# TK90X.net
KiCad netlist of a schematic drawn in EAGLE
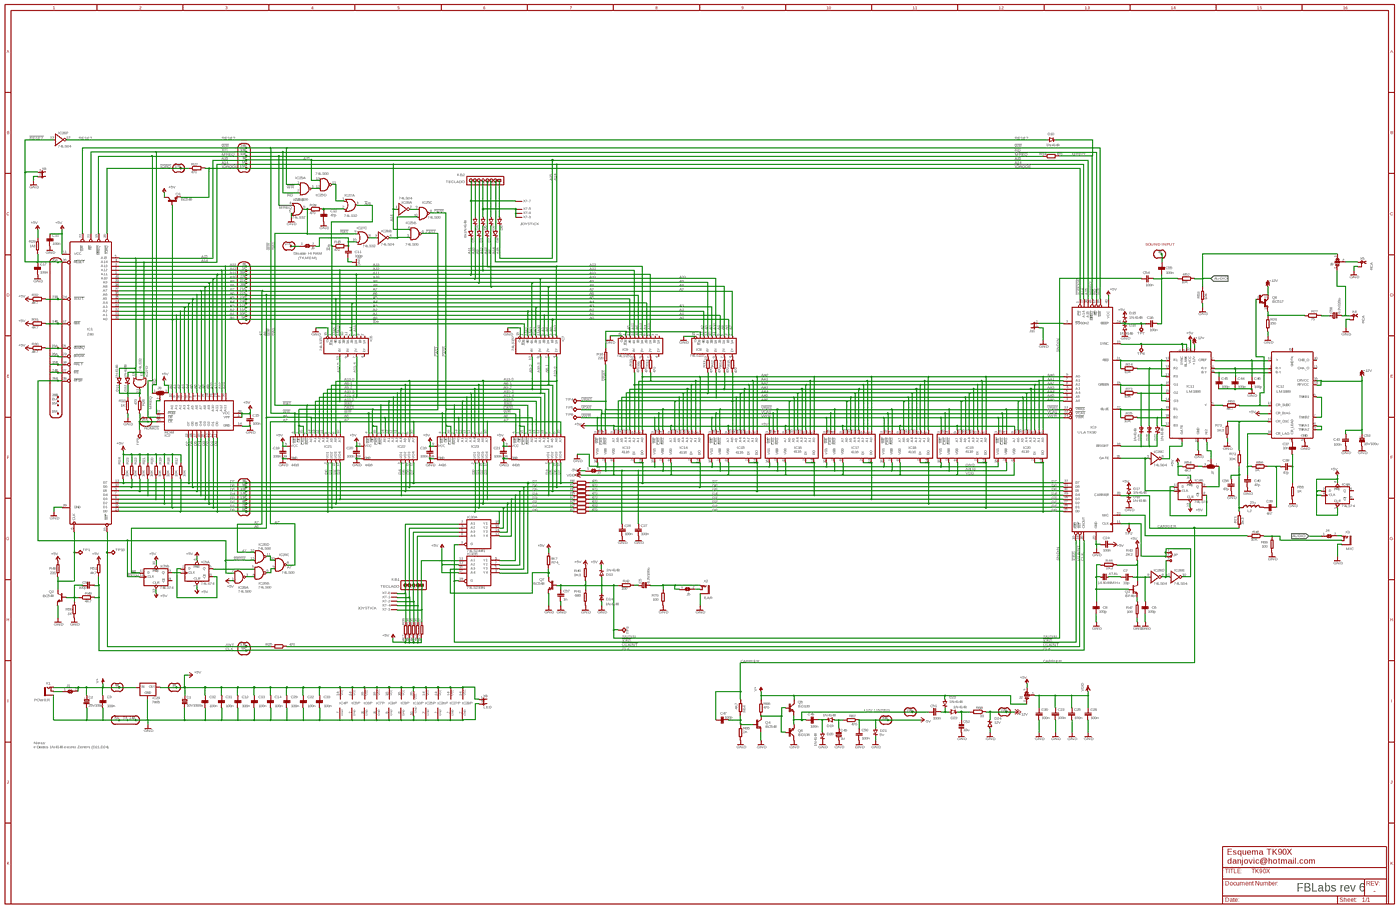
[diagram p0: schematic, sheet 1, overview]
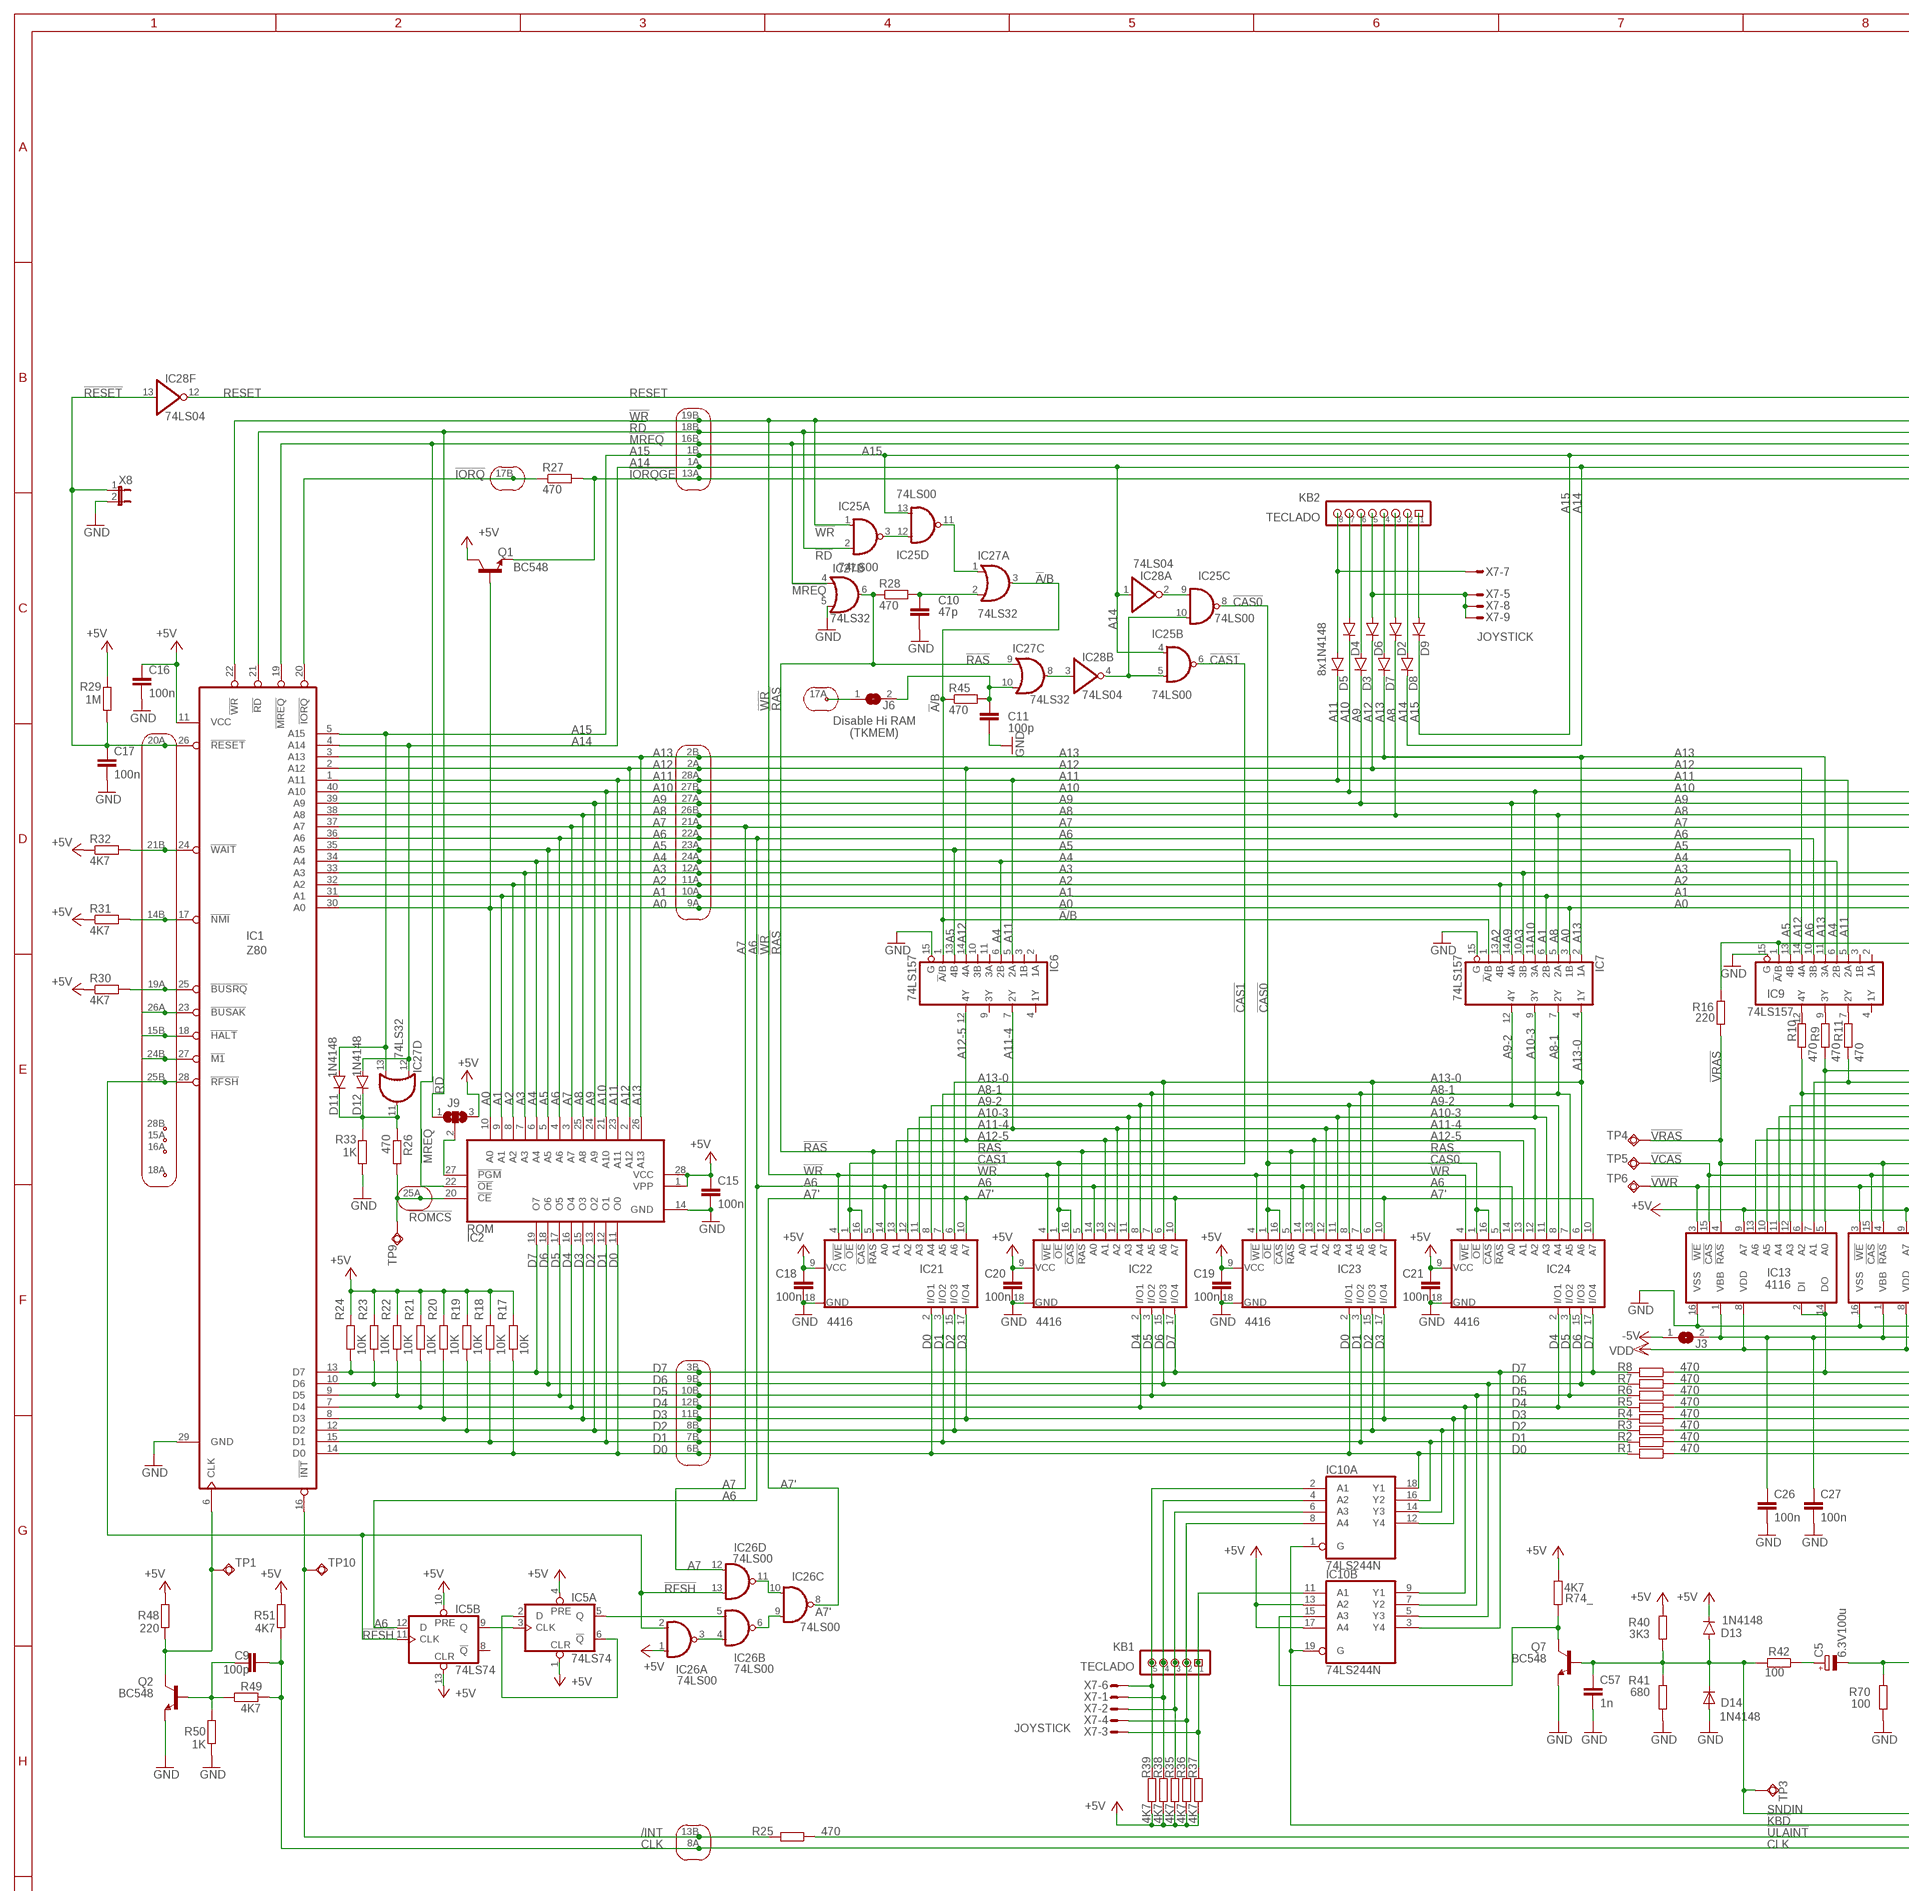
[diagram p1: schematic, sheet 1, part 1 of 4]
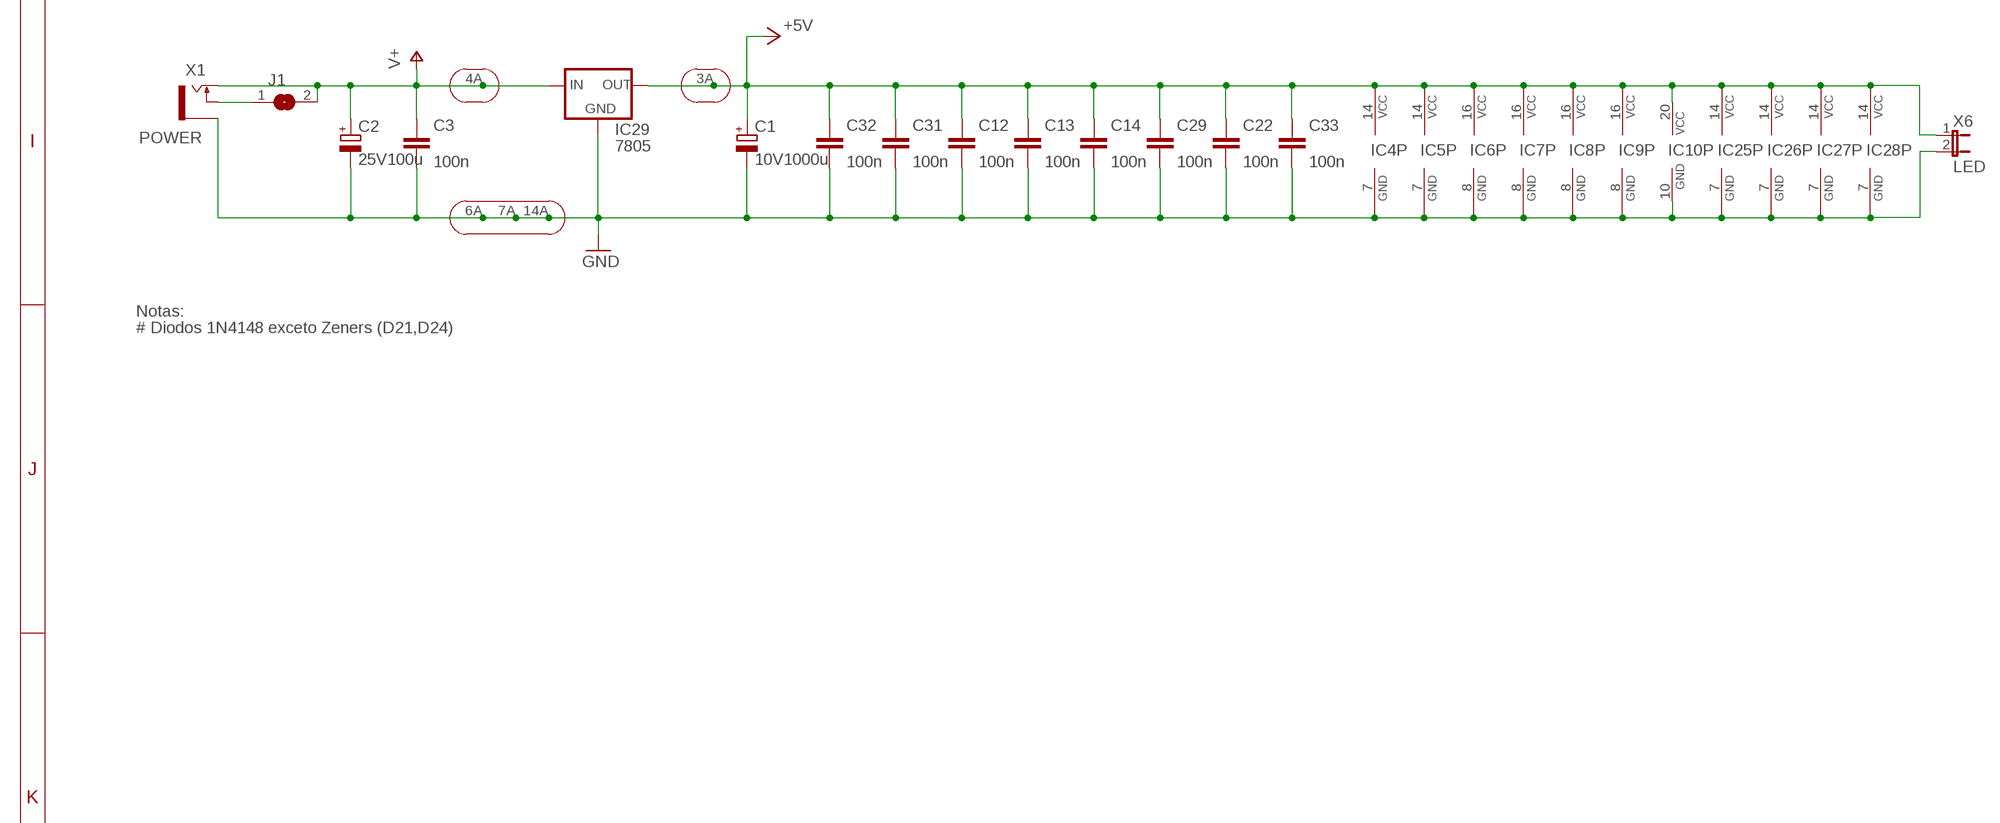
[diagram p2: schematic, sheet 1, part 2 of 4]
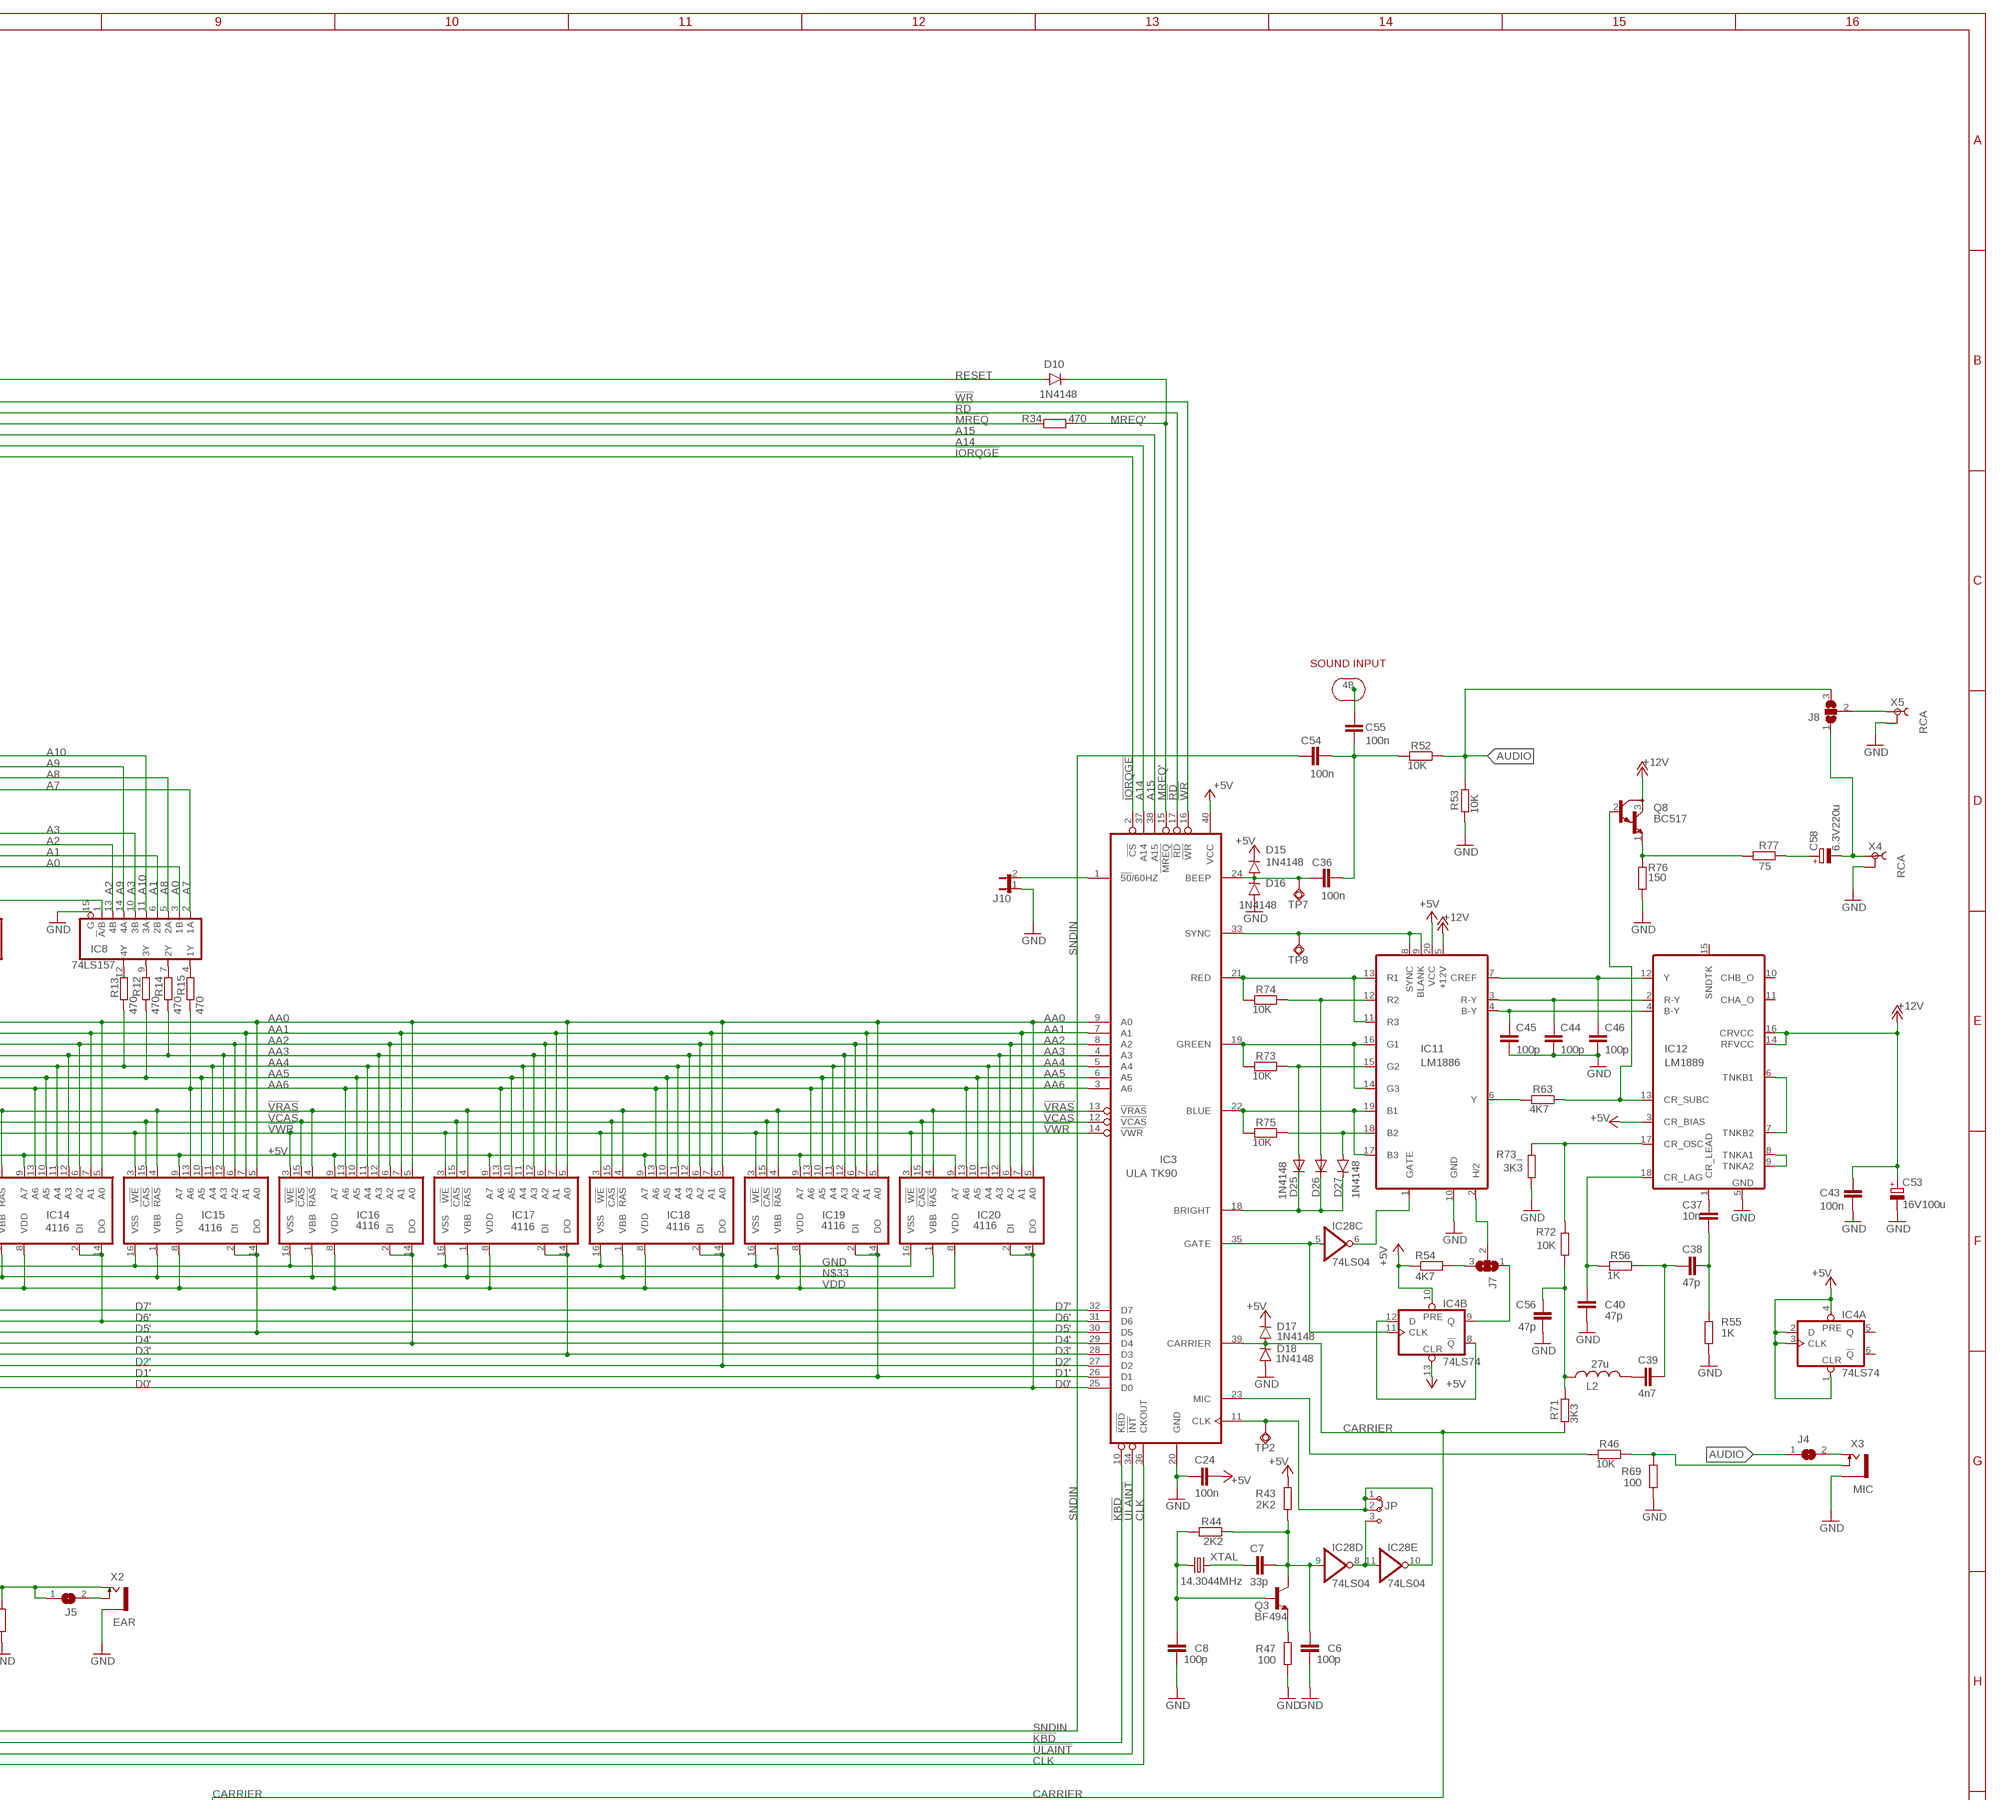
[diagram p3: schematic, sheet 1, part 3 of 4]
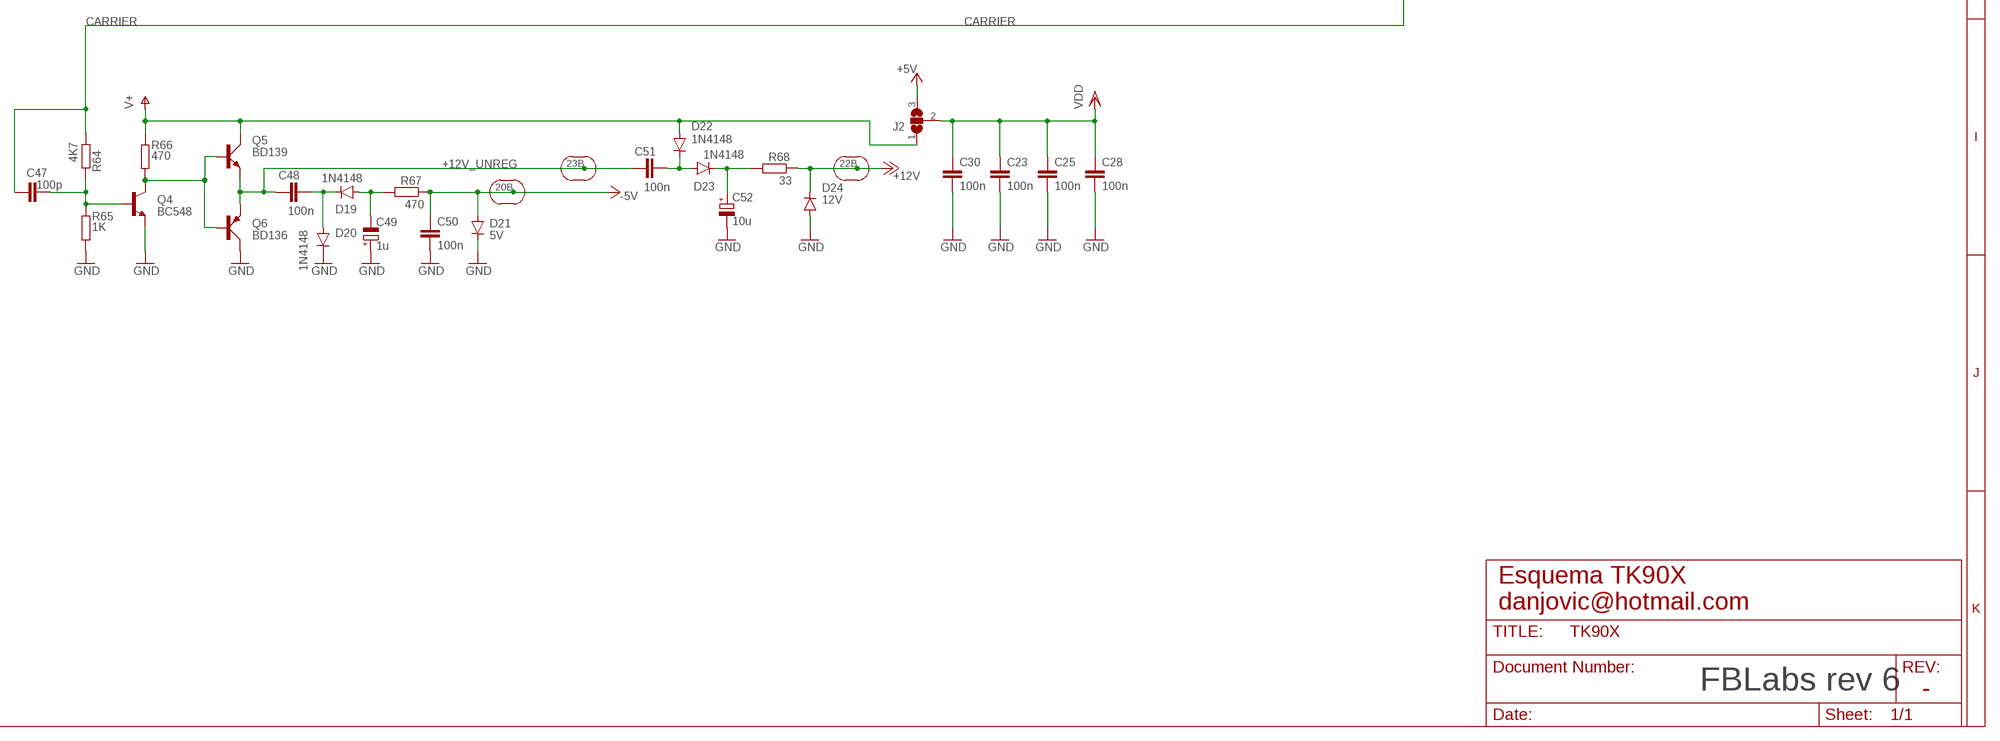
[diagram p4: schematic, sheet 1, part 4 of 4]

(export (version "E")
  (design (tool "Eeschema 10.0.6"))
  (components
    (comp (ref "C1")
      (value "10V1000u")
      (footprint "eagle-import:E5-8,5")
      (libsource (lib "eagle-import") (part "CPOL-EUE5-8.5"))
    )
    (comp (ref "C2")
      (value "25V100u")
      (footprint "eagle-import:E5-6")
      (libsource (lib "eagle-import") (part "CPOL-EUE5-6"))
    )
    (comp (ref "C3")
      (value "100n")
      (footprint "eagle-import:C050-024X044")
      (libsource (lib "eagle-import") (part "C-EU050-024X044"))
    )
    (comp (ref "C5")
      (value "6.3V100u")
      (footprint "eagle-import:E5-4")
      (libsource (lib "eagle-import") (part "tk90_CPOL-EUE5-4"))
    )
    (comp (ref "C6")
      (value "100p")
      (footprint "eagle-import:C050-024X044")
      (libsource (lib "eagle-import") (part "C-EU050-024X044"))
    )
    (comp (ref "C7")
      (value "33p")
      (footprint "eagle-import:C050-024X044")
      (libsource (lib "eagle-import") (part "C-EU050-024X044"))
    )
    (comp (ref "C8")
      (value "100p")
      (footprint "eagle-import:C050-024X044")
      (libsource (lib "eagle-import") (part "C-EU050-024X044"))
    )
    (comp (ref "C9")
      (value "100p")
      (footprint "eagle-import:C050-024X044")
      (libsource (lib "eagle-import") (part "C-EU050-024X044"))
    )
    (comp (ref "C10")
      (value "47p")
      (footprint "eagle-import:C050-024X044")
      (libsource (lib "eagle-import") (part "C-EU050-024X044"))
    )
    (comp (ref "C11")
      (value "100p")
      (footprint "eagle-import:C050-024X044")
      (libsource (lib "eagle-import") (part "C-EU050-024X044"))
    )
    (comp (ref "C12")
      (value "100n")
      (footprint "eagle-import:C050-024X044")
      (libsource (lib "eagle-import") (part "C-EU050-024X044"))
    )
    (comp (ref "C13")
      (value "100n")
      (footprint "eagle-import:C050-024X044")
      (libsource (lib "eagle-import") (part "C-EU050-024X044"))
    )
    (comp (ref "C14")
      (value "100n")
      (footprint "eagle-import:C050-024X044")
      (libsource (lib "eagle-import") (part "C-EU050-024X044"))
    )
    (comp (ref "C15")
      (value "100n")
      (footprint "eagle-import:C050-024X044")
      (libsource (lib "eagle-import") (part "C-EU050-024X044"))
    )
    (comp (ref "C16")
      (value "100n")
      (footprint "eagle-import:C050-024X044")
      (libsource (lib "eagle-import") (part "C-EU050-024X044"))
    )
    (comp (ref "C17")
      (value "100n")
      (footprint "eagle-import:C050-024X044")
      (libsource (lib "eagle-import") (part "C-EU050-024X044"))
    )
    (comp (ref "C18")
      (value "100n")
      (footprint "eagle-import:C050-024X044")
      (libsource (lib "eagle-import") (part "C-EU050-024X044"))
    )
    (comp (ref "C19")
      (value "100n")
      (footprint "eagle-import:C050-024X044")
      (libsource (lib "eagle-import") (part "C-EU050-024X044"))
    )
    (comp (ref "C20")
      (value "100n")
      (footprint "eagle-import:C050-024X044")
      (libsource (lib "eagle-import") (part "C-EU050-024X044"))
    )
    (comp (ref "C21")
      (value "100n")
      (footprint "eagle-import:C050-024X044")
      (libsource (lib "eagle-import") (part "C-EU050-024X044"))
    )
    (comp (ref "C22")
      (value "100n")
      (footprint "eagle-import:C050-024X044")
      (libsource (lib "eagle-import") (part "C-EU050-024X044"))
    )
    (comp (ref "C23")
      (value "100n")
      (footprint "eagle-import:C050-024X044")
      (libsource (lib "eagle-import") (part "C-EU050-024X044"))
    )
    (comp (ref "C24")
      (value "100n")
      (footprint "eagle-import:C050-024X044")
      (libsource (lib "eagle-import") (part "C-EU050-024X044"))
    )
    (comp (ref "C25")
      (value "100n")
      (footprint "eagle-import:C050-024X044")
      (libsource (lib "eagle-import") (part "C-EU050-024X044"))
    )
    (comp (ref "C26")
      (value "100n")
      (footprint "eagle-import:C050-024X044")
      (libsource (lib "eagle-import") (part "C-EU050-024X044"))
    )
    (comp (ref "C27")
      (value "100n")
      (footprint "eagle-import:C050-024X044")
      (libsource (lib "eagle-import") (part "C-EU050-024X044"))
    )
    (comp (ref "C28")
      (value "100n")
      (footprint "eagle-import:C050-024X044")
      (libsource (lib "eagle-import") (part "C-EU050-024X044"))
    )
    (comp (ref "C29")
      (value "100n")
      (footprint "eagle-import:C050-024X044")
      (libsource (lib "eagle-import") (part "C-EU050-024X044"))
    )
    (comp (ref "C30")
      (value "100n")
      (footprint "eagle-import:C050-024X044")
      (libsource (lib "eagle-import") (part "C-EU050-024X044"))
    )
    (comp (ref "C31")
      (value "100n")
      (footprint "eagle-import:C050-024X044")
      (libsource (lib "eagle-import") (part "C-EU050-024X044"))
    )
    (comp (ref "C32")
      (value "100n")
      (footprint "eagle-import:C050-024X044")
      (libsource (lib "eagle-import") (part "C-EU050-024X044"))
    )
    (comp (ref "C33")
      (value "100n")
      (footprint "eagle-import:C050-024X044")
      (libsource (lib "eagle-import") (part "C-EU050-024X044"))
    )
    (comp (ref "C36")
      (value "100n")
      (footprint "eagle-import:C050-024X044")
      (libsource (lib "eagle-import") (part "C-EU050-024X044"))
    )
    (comp (ref "C37")
      (value "10n")
      (footprint "eagle-import:C050-024X044")
      (libsource (lib "eagle-import") (part "C-EU050-024X044"))
    )
    (comp (ref "C38")
      (value "47p")
      (footprint "eagle-import:C050-024X044")
      (libsource (lib "eagle-import") (part "C-EU050-024X044"))
    )
    (comp (ref "C39")
      (value "4n7")
      (footprint "eagle-import:C050-024X044")
      (libsource (lib "eagle-import") (part "C-EU050-024X044"))
    )
    (comp (ref "C40")
      (value "47p")
      (footprint "eagle-import:C050-024X044")
      (libsource (lib "eagle-import") (part "C-EU050-024X044"))
    )
    (comp (ref "C43")
      (value "100n")
      (footprint "eagle-import:C050-024X044")
      (libsource (lib "eagle-import") (part "C-EU050-024X044"))
    )
    (comp (ref "C44")
      (value "100p")
      (footprint "eagle-import:C050-024X044")
      (libsource (lib "eagle-import") (part "C-EU050-024X044"))
    )
    (comp (ref "C45")
      (value "100p")
      (footprint "eagle-import:C050-024X044")
      (libsource (lib "eagle-import") (part "C-EU050-024X044"))
    )
    (comp (ref "C46")
      (value "100p")
      (footprint "eagle-import:C050-024X044")
      (libsource (lib "eagle-import") (part "C-EU050-024X044"))
    )
    (comp (ref "C47")
      (value "100p")
      (footprint "eagle-import:C050-024X044")
      (libsource (lib "eagle-import") (part "C-EU050-024X044"))
    )
    (comp (ref "C48")
      (value "100n")
      (footprint "eagle-import:C050-024X044")
      (libsource (lib "eagle-import") (part "C-EU050-024X044"))
    )
    (comp (ref "C49")
      (value "1u")
      (footprint "eagle-import:E2-4")
      (libsource (lib "eagle-import") (part "CPOL-EUE2-4"))
    )
    (comp (ref "C50")
      (value "100n")
      (footprint "eagle-import:C050-024X044")
      (libsource (lib "eagle-import") (part "C-EU050-024X044"))
    )
    (comp (ref "C51")
      (value "100n")
      (footprint "eagle-import:C050-024X044")
      (libsource (lib "eagle-import") (part "C-EU050-024X044"))
    )
    (comp (ref "C52")
      (value "10u")
      (footprint "eagle-import:E2-4")
      (libsource (lib "eagle-import") (part "CPOL-EUE2-4"))
    )
    (comp (ref "C53")
      (value "16V100u")
      (footprint "eagle-import:E5-5")
      (libsource (lib "eagle-import") (part "CPOL-EUE5-5"))
    )
    (comp (ref "C54")
      (value "100n")
      (footprint "eagle-import:C050-024X044")
      (libsource (lib "eagle-import") (part "C-EU050-024X044"))
    )
    (comp (ref "C55")
      (value "100n")
      (footprint "eagle-import:C050-024X044")
      (libsource (lib "eagle-import") (part "C-EU050-024X044"))
    )
    (comp (ref "C56")
      (value "47p")
      (footprint "eagle-import:C050-024X044")
      (libsource (lib "eagle-import") (part "C-EU050-024X044"))
    )
    (comp (ref "C57")
      (value "1n")
      (footprint "eagle-import:C050-024X044")
      (libsource (lib "eagle-import") (part "C-EU050-024X044"))
    )
    (comp (ref "C58")
      (value "6.3V220u")
      (footprint "eagle-import:E5-6")
      (libsource (lib "eagle-import") (part "CPOL-EUE5-6"))
    )
    (comp (ref "D2")
      (value "1N4148")
      (footprint "eagle-import:DO35-12")
      (libsource (lib "eagle-import") (part "DDO35-12"))
    )
    (comp (ref "D3")
      (value "1N4148")
      (footprint "eagle-import:DO35-12")
      (libsource (lib "eagle-import") (part "DDO35-12"))
    )
    (comp (ref "D4")
      (value "1N4148")
      (footprint "eagle-import:DO35-12")
      (libsource (lib "eagle-import") (part "DDO35-12"))
    )
    (comp (ref "D5")
      (value "1N4148")
      (footprint "eagle-import:DO35-12")
      (libsource (lib "eagle-import") (part "DDO35-12"))
    )
    (comp (ref "D6")
      (value "1N4148")
      (footprint "eagle-import:DO35-12")
      (libsource (lib "eagle-import") (part "DDO35-12"))
    )
    (comp (ref "D7")
      (value "1N4148")
      (footprint "eagle-import:DO35-12")
      (libsource (lib "eagle-import") (part "DDO35-12"))
    )
    (comp (ref "D8")
      (value "1N4148")
      (footprint "eagle-import:DO35-12")
      (libsource (lib "eagle-import") (part "DDO35-12"))
    )
    (comp (ref "D9")
      (value "1N4148")
      (footprint "eagle-import:DO35-12")
      (libsource (lib "eagle-import") (part "DDO35-12"))
    )
    (comp (ref "D10")
      (value "1N4148")
      (footprint "eagle-import:DO35-12")
      (libsource (lib "eagle-import") (part "DDO35-12"))
    )
    (comp (ref "D11")
      (value "1N4148")
      (footprint "eagle-import:DO35-12")
      (libsource (lib "eagle-import") (part "DDO35-12"))
    )
    (comp (ref "D12")
      (value "1N4148")
      (footprint "eagle-import:DO35-12")
      (libsource (lib "eagle-import") (part "DDO35-12"))
    )
    (comp (ref "D13")
      (value "1N4148")
      (footprint "eagle-import:DO35-12")
      (libsource (lib "eagle-import") (part "DDO35-12"))
    )
    (comp (ref "D14")
      (value "1N4148")
      (footprint "eagle-import:D-5")
      (libsource (lib "eagle-import") (part "DIODE-D-5"))
    )
    (comp (ref "D15")
      (value "1N4148")
      (footprint "eagle-import:DO35-12")
      (libsource (lib "eagle-import") (part "DDO35-12"))
    )
    (comp (ref "D16")
      (value "1N4148")
      (footprint "eagle-import:DO35-12")
      (libsource (lib "eagle-import") (part "DDO35-12"))
    )
    (comp (ref "D17")
      (value "1N4148")
      (footprint "eagle-import:DO35-12")
      (libsource (lib "eagle-import") (part "DDO35-12"))
    )
    (comp (ref "D18")
      (value "1N4148")
      (footprint "eagle-import:DO35-12")
      (libsource (lib "eagle-import") (part "DDO35-12"))
    )
    (comp (ref "D19")
      (value "1N4148")
      (footprint "eagle-import:DO35-12")
      (libsource (lib "eagle-import") (part "DDO35-12"))
    )
    (comp (ref "D20")
      (value "1N4148")
      (footprint "eagle-import:DO35-12")
      (libsource (lib "eagle-import") (part "DDO35-12"))
    )
    (comp (ref "D21")
      (value "5V")
      (footprint "eagle-import:DO35-12")
      (libsource (lib "eagle-import") (part "DDO35-12"))
    )
    (comp (ref "D22")
      (value "1N4148")
      (footprint "eagle-import:DO35-12")
      (libsource (lib "eagle-import") (part "DDO35-12"))
    )
    (comp (ref "D23")
      (value "1N4148")
      (footprint "eagle-import:DO35-12")
      (libsource (lib "eagle-import") (part "DDO35-12"))
    )
    (comp (ref "D24")
      (value "12V")
      (footprint "eagle-import:DO35-12")
      (libsource (lib "eagle-import") (part "DDO35-12"))
    )
    (comp (ref "D25")
      (value "1N4148")
      (footprint "eagle-import:D-5")
      (libsource (lib "eagle-import") (part "DIODE-D-5"))
    )
    (comp (ref "D26")
      (value "1N4148")
      (footprint "eagle-import:D-5")
      (libsource (lib "eagle-import") (part "DIODE-D-5"))
    )
    (comp (ref "D27")
      (value "1N4148")
      (footprint "eagle-import:DO35-12")
      (libsource (lib "eagle-import") (part "DDO35-12"))
    )
    (comp (ref "IC1")
      (value "Z80")
      (footprint "eagle-import:DIL40")
      (libsource (lib "eagle-import") (part "Z80CPU"))
    )
    (comp (ref "IC2")
      (value "ROM")
      (footprint "eagle-import:DIL28")
      (libsource (lib "eagle-import") (part "25128"))
    )
    (comp (ref "IC3")
      (value "ULA TK90")
      (footprint "eagle-import:DIL40")
      (libsource (lib "eagle-import") (part "ULA-TK90"))
    )
    (comp (ref "IC4")
      (value "74LS74")
      (footprint "eagle-import:DIL14")
      (libsource (lib "eagle-import") (part "7474NLS"))
    )
    (comp (ref "IC5")
      (value "74LS74")
      (footprint "eagle-import:DIL14")
      (libsource (lib "eagle-import") (part "7474NLS"))
    )
    (comp (ref "IC6")
      (value "74LS157")
      (footprint "eagle-import:DIL16")
      (libsource (lib "eagle-import") (part "74157NS"))
    )
    (comp (ref "IC7")
      (value "74LS157")
      (footprint "eagle-import:DIL16")
      (libsource (lib "eagle-import") (part "74157NS"))
    )
    (comp (ref "IC8")
      (value "74LS157")
      (footprint "eagle-import:DIL16")
      (libsource (lib "eagle-import") (part "74157NS"))
    )
    (comp (ref "IC9")
      (value "74LS157")
      (footprint "eagle-import:DIL16")
      (libsource (lib "eagle-import") (part "74157NS"))
    )
    (comp (ref "IC10")
      (value "74LS244N")
      (footprint "eagle-import:DIL20")
      (libsource (lib "eagle-import") (part "74244NLS"))
    )
    (comp (ref "IC11")
      (value "LM1886")
      (footprint "eagle-import:DIL20")
      (libsource (lib "eagle-import") (part "LM1886N"))
    )
    (comp (ref "IC12")
      (value "LM1889")
      (footprint "eagle-import:DIL18")
      (libsource (lib "eagle-import") (part "LM1889"))
    )
    (comp (ref "IC13")
      (value "4116")
      (footprint "eagle-import:DIL16")
      (libsource (lib "eagle-import") (part "MK4516"))
    )
    (comp (ref "IC14")
      (value "4116")
      (footprint "eagle-import:DIL16")
      (libsource (lib "eagle-import") (part "MK4516"))
    )
    (comp (ref "IC15")
      (value "4116")
      (footprint "eagle-import:DIL16")
      (libsource (lib "eagle-import") (part "MK4516"))
    )
    (comp (ref "IC16")
      (value "4116")
      (footprint "eagle-import:DIL16")
      (libsource (lib "eagle-import") (part "MK4516"))
    )
    (comp (ref "IC17")
      (value "4116")
      (footprint "eagle-import:DIL16")
      (libsource (lib "eagle-import") (part "MK4516"))
    )
    (comp (ref "IC18")
      (value "4116")
      (footprint "eagle-import:DIL16")
      (libsource (lib "eagle-import") (part "MK4516"))
    )
    (comp (ref "IC19")
      (value "4116")
      (footprint "eagle-import:DIL16")
      (libsource (lib "eagle-import") (part "MK4516"))
    )
    (comp (ref "IC20")
      (value "4116")
      (footprint "eagle-import:DIL16")
      (libsource (lib "eagle-import") (part "MK4516"))
    )
    (comp (ref "IC21")
      (value "4416")
      (footprint "eagle-import:DIL18")
      (libsource (lib "eagle-import") (part "4416"))
    )
    (comp (ref "IC22")
      (value "4416")
      (footprint "eagle-import:DIL18")
      (libsource (lib "eagle-import") (part "4416"))
    )
    (comp (ref "IC23")
      (value "4416")
      (footprint "eagle-import:DIL18")
      (libsource (lib "eagle-import") (part "4416"))
    )
    (comp (ref "IC24")
      (value "4416")
      (footprint "eagle-import:DIL18")
      (libsource (lib "eagle-import") (part "4416"))
    )
    (comp (ref "IC25")
      (value "74LS00")
      (footprint "eagle-import:DIL14")
      (libsource (lib "eagle-import") (part "7400NLS"))
    )
    (comp (ref "IC26")
      (value "74LS00")
      (footprint "eagle-import:DIL14")
      (libsource (lib "eagle-import") (part "7400NLS"))
    )
    (comp (ref "IC27")
      (value "74LS32")
      (footprint "eagle-import:DIL14")
      (libsource (lib "eagle-import") (part "7432NLS"))
    )
    (comp (ref "IC28")
      (value "74LS04")
      (footprint "eagle-import:DIL14")
      (libsource (lib "eagle-import") (part "7404NLS"))
    )
    (comp (ref "IC29")
      (value "7805")
      (footprint "eagle-import:78XXL")
      (libsource (lib "eagle-import") (part "78XXL"))
    )
    (comp (ref "J1") (value "SJ") (footprint "eagle-import:SJ") (libsource (lib "eagle-import") (part "SJ")))
    (comp (ref "J2")
      (value "SJ2W")
      (footprint "eagle-import:SJ_2")
      (libsource (lib "eagle-import") (part "SJ2W"))
    )
    (comp (ref "J3") (value "SJ") (footprint "eagle-import:SJ") (libsource (lib "eagle-import") (part "SJ")))
    (comp (ref "J4") (value "SJ") (footprint "eagle-import:SJ") (libsource (lib "eagle-import") (part "SJ")))
    (comp (ref "J5") (value "SJ") (footprint "eagle-import:SJ") (libsource (lib "eagle-import") (part "SJ")))
    (comp (ref "J6") (value "SJ") (footprint "eagle-import:SJ") (libsource (lib "eagle-import") (part "SJ")))
    (comp (ref "J7")
      (value "SJ2W")
      (footprint "eagle-import:SJ_2")
      (libsource (lib "eagle-import") (part "SJ2W"))
    )
    (comp (ref "J8")
      (value "SJ2W")
      (footprint "eagle-import:SJ_2")
      (libsource (lib "eagle-import") (part "SJ2W"))
    )
    (comp (ref "J9")
      (value "SJ2W")
      (footprint "eagle-import:SJ_2")
      (libsource (lib "eagle-import") (part "SJ2W"))
    )
    (comp (ref "J10")
      (value "JP1E")
      (footprint "eagle-import:JP1")
      (libsource (lib "eagle-import") (part "JP1E"))
    )
    (comp (ref "JP")
      (value "J2X1MM")
      (footprint "eagle-import:03C")
      (libsource (lib "eagle-import") (part "J2X1MM"))
    )
    (comp (ref "KB1")
      (value "TECLADO")
      (footprint "eagle-import:FE05-1")
      (libsource (lib "eagle-import") (part "CON-TECL-5"))
    )
    (comp (ref "KB2")
      (value "TECLADO")
      (footprint "eagle-import:FE08")
      (libsource (lib "eagle-import") (part "CON-TECL-8"))
    )
    (comp (ref "L2")
      (value "27u")
      (footprint "eagle-import:0207_7")
      (libsource (lib "eagle-import") (part "L-US0207/7"))
    )
    (comp (ref "Q1")
      (value "BC548")
      (footprint "eagle-import:TO92L")
      (libsource (lib "eagle-import") (part "-NPN-TO92L"))
    )
    (comp (ref "Q2")
      (value "BC548")
      (footprint "eagle-import:TO92L")
      (libsource (lib "eagle-import") (part "-NPN-TO92L"))
    )
    (comp (ref "Q3")
      (value "BF494")
      (footprint "eagle-import:TO92-CEB")
      (libsource (lib "eagle-import") (part "BF494"))
    )
    (comp (ref "Q4")
      (value "BC548")
      (footprint "eagle-import:TO92L")
      (libsource (lib "eagle-import") (part "-NPN-TO92L"))
    )
    (comp (ref "Q5")
      (value "BD139")
      (footprint "eagle-import:TO126AV")
      (libsource (lib "eagle-import") (part "BD139"))
    )
    (comp (ref "Q6")
      (value "BD136")
      (footprint "eagle-import:TO126AV")
      (libsource (lib "eagle-import") (part "BD140"))
    )
    (comp (ref "Q7")
      (value "BC548")
      (footprint "eagle-import:TO92L")
      (libsource (lib "eagle-import") (part "-NPN-TO92L"))
    )
    (comp (ref "Q8")
      (value "BC517")
      (footprint "eagle-import:TO92")
      (libsource (lib "eagle-import") (part "BC517"))
    )
    (comp (ref "R1")
      (value "470")
      (footprint "eagle-import:0207_12")
      (libsource (lib "eagle-import") (part "R-EU_0207/12"))
    )
    (comp (ref "R2")
      (value "470")
      (footprint "eagle-import:0207_12")
      (libsource (lib "eagle-import") (part "R-EU_0207/12"))
    )
    (comp (ref "R3")
      (value "470")
      (footprint "eagle-import:0207_12")
      (libsource (lib "eagle-import") (part "R-EU_0207/12"))
    )
    (comp (ref "R4")
      (value "470")
      (footprint "eagle-import:0207_12")
      (libsource (lib "eagle-import") (part "R-EU_0207/12"))
    )
    (comp (ref "R5")
      (value "470")
      (footprint "eagle-import:0207_12")
      (libsource (lib "eagle-import") (part "R-EU_0207/12"))
    )
    (comp (ref "R6")
      (value "470")
      (footprint "eagle-import:0207_12")
      (libsource (lib "eagle-import") (part "R-EU_0207/12"))
    )
    (comp (ref "R7")
      (value "470")
      (footprint "eagle-import:0207_12")
      (libsource (lib "eagle-import") (part "R-EU_0207/12"))
    )
    (comp (ref "R8")
      (value "470")
      (footprint "eagle-import:0207_12")
      (libsource (lib "eagle-import") (part "R-EU_0207/12"))
    )
    (comp (ref "R9")
      (value "470")
      (footprint "eagle-import:0207_12")
      (libsource (lib "eagle-import") (part "R-EU_0207/12"))
    )
    (comp (ref "R10")
      (value "470")
      (footprint "eagle-import:0207_12")
      (libsource (lib "eagle-import") (part "R-EU_0207/12"))
    )
    (comp (ref "R11")
      (value "470")
      (footprint "eagle-import:0207_12")
      (libsource (lib "eagle-import") (part "R-EU_0207/12"))
    )
    (comp (ref "R12")
      (value "470")
      (footprint "eagle-import:0207_12")
      (libsource (lib "eagle-import") (part "R-EU_0207/12"))
    )
    (comp (ref "R13")
      (value "470")
      (footprint "eagle-import:0207_12")
      (libsource (lib "eagle-import") (part "R-EU_0207/12"))
    )
    (comp (ref "R14")
      (value "470")
      (footprint "eagle-import:0207_12")
      (libsource (lib "eagle-import") (part "R-EU_0207/12"))
    )
    (comp (ref "R15")
      (value "470")
      (footprint "eagle-import:0207_12")
      (libsource (lib "eagle-import") (part "R-EU_0207/12"))
    )
    (comp (ref "R16")
      (value "220")
      (footprint "eagle-import:0207_12")
      (libsource (lib "eagle-import") (part "R-EU_0207/12"))
    )
    (comp (ref "R17")
      (value "10K")
      (footprint "eagle-import:0207_12")
      (libsource (lib "eagle-import") (part "R-EU_0207/12"))
    )
    (comp (ref "R18")
      (value "10K")
      (footprint "eagle-import:0207_12")
      (libsource (lib "eagle-import") (part "R-EU_0207/12"))
    )
    (comp (ref "R19")
      (value "10K")
      (footprint "eagle-import:0207_12")
      (libsource (lib "eagle-import") (part "R-EU_0207/12"))
    )
    (comp (ref "R20")
      (value "10K")
      (footprint "eagle-import:0207_12")
      (libsource (lib "eagle-import") (part "R-EU_0207/12"))
    )
    (comp (ref "R21")
      (value "10K")
      (footprint "eagle-import:0207_12")
      (libsource (lib "eagle-import") (part "R-EU_0207/12"))
    )
    (comp (ref "R22")
      (value "10K")
      (footprint "eagle-import:0207_12")
      (libsource (lib "eagle-import") (part "R-EU_0207/12"))
    )
    (comp (ref "R23")
      (value "10K")
      (footprint "eagle-import:0207_12")
      (libsource (lib "eagle-import") (part "R-EU_0207/12"))
    )
    (comp (ref "R24")
      (value "10K")
      (footprint "eagle-import:0207_12")
      (libsource (lib "eagle-import") (part "R-EU_0207/12"))
    )
    (comp (ref "R25")
      (value "470")
      (footprint "eagle-import:0207_12")
      (libsource (lib "eagle-import") (part "R-EU_0207/12"))
    )
    (comp (ref "R26")
      (value "470")
      (footprint "eagle-import:0207_12")
      (libsource (lib "eagle-import") (part "R-EU_0207/12"))
    )
    (comp (ref "R27")
      (value "470")
      (footprint "eagle-import:0207_12")
      (libsource (lib "eagle-import") (part "R-EU_0207/12"))
    )
    (comp (ref "R28")
      (value "470")
      (footprint "eagle-import:0207_12")
      (libsource (lib "eagle-import") (part "R-EU_0207/12"))
    )
    (comp (ref "R29")
      (value "1M")
      (footprint "eagle-import:0207_12")
      (libsource (lib "eagle-import") (part "R-EU_0207/12"))
    )
    (comp (ref "R30")
      (value "4K7")
      (footprint "eagle-import:0207_12")
      (libsource (lib "eagle-import") (part "R-EU_0207/12"))
    )
    (comp (ref "R31")
      (value "4K7")
      (footprint "eagle-import:0207_12")
      (libsource (lib "eagle-import") (part "R-EU_0207/12"))
    )
    (comp (ref "R32")
      (value "4K7")
      (footprint "eagle-import:0207_12")
      (libsource (lib "eagle-import") (part "R-EU_0207/12"))
    )
    (comp (ref "R33")
      (value "1K")
      (footprint "eagle-import:0207_12")
      (libsource (lib "eagle-import") (part "R-EU_0207/12"))
    )
    (comp (ref "R34")
      (value "470")
      (footprint "eagle-import:0207_12")
      (libsource (lib "eagle-import") (part "R-EU_0207/12"))
    )
    (comp (ref "R35")
      (value "4K7")
      (footprint "eagle-import:0207_12")
      (libsource (lib "eagle-import") (part "R-EU_0207/12"))
    )
    (comp (ref "R36")
      (value "4K7")
      (footprint "eagle-import:0207_12")
      (libsource (lib "eagle-import") (part "R-EU_0207/12"))
    )
    (comp (ref "R37")
      (value "4K7")
      (footprint "eagle-import:0207_12")
      (libsource (lib "eagle-import") (part "R-EU_0207/12"))
    )
    (comp (ref "R38")
      (value "4K7")
      (footprint "eagle-import:0207_12")
      (libsource (lib "eagle-import") (part "R-EU_0207/12"))
    )
    (comp (ref "R39")
      (value "4K7")
      (footprint "eagle-import:0207_12")
      (libsource (lib "eagle-import") (part "R-EU_0207/12"))
    )
    (comp (ref "R40")
      (value "3K3")
      (footprint "eagle-import:0207_12")
      (libsource (lib "eagle-import") (part "R-EU_0207/12"))
    )
    (comp (ref "R41")
      (value "680")
      (footprint "eagle-import:0207_5V")
      (libsource (lib "eagle-import") (part "R-EU_0207/5V"))
    )
    (comp (ref "R42")
      (value "100")
      (footprint "eagle-import:0207_5V")
      (libsource (lib "eagle-import") (part "R-EU_0207/5V"))
    )
    (comp (ref "R43")
      (value "2K2")
      (footprint "eagle-import:0207_12")
      (libsource (lib "eagle-import") (part "R-EU_0207/12"))
    )
    (comp (ref "R44")
      (value "2K2")
      (footprint "eagle-import:0207_12")
      (libsource (lib "eagle-import") (part "R-EU_0207/12"))
    )
    (comp (ref "R45")
      (value "470")
      (footprint "eagle-import:0207_12")
      (libsource (lib "eagle-import") (part "R-EU_0207/12"))
    )
    (comp (ref "R46")
      (value "10K")
      (footprint "eagle-import:0207_12")
      (libsource (lib "eagle-import") (part "R-EU_0207/12"))
    )
    (comp (ref "R47")
      (value "100")
      (footprint "eagle-import:0207_12")
      (libsource (lib "eagle-import") (part "R-EU_0207/12"))
    )
    (comp (ref "R48")
      (value "220")
      (footprint "eagle-import:0207_12")
      (libsource (lib "eagle-import") (part "R-EU_0207/12"))
    )
    (comp (ref "R49")
      (value "4K7")
      (footprint "eagle-import:0207_12")
      (libsource (lib "eagle-import") (part "R-EU_0207/12"))
    )
    (comp (ref "R50")
      (value "1K")
      (footprint "eagle-import:0207_12")
      (libsource (lib "eagle-import") (part "R-EU_0207/12"))
    )
    (comp (ref "R51")
      (value "4K7")
      (footprint "eagle-import:0207_12")
      (libsource (lib "eagle-import") (part "R-EU_0207/12"))
    )
    (comp (ref "R52")
      (value "10K")
      (footprint "eagle-import:0207_5V")
      (libsource (lib "eagle-import") (part "R-EU_0207/5V"))
    )
    (comp (ref "R53")
      (value "10K")
      (footprint "eagle-import:0207_5V")
      (libsource (lib "eagle-import") (part "R-EU_0207/5V"))
    )
    (comp (ref "R54")
      (value "4K7")
      (footprint "eagle-import:0207_12")
      (libsource (lib "eagle-import") (part "R-EU_0207/12"))
    )
    (comp (ref "R55")
      (value "1K")
      (footprint "eagle-import:0207_5V")
      (libsource (lib "eagle-import") (part "R-EU_0207/5V"))
    )
    (comp (ref "R56")
      (value "1K")
      (footprint "eagle-import:0207_5V")
      (libsource (lib "eagle-import") (part "R-EU_0207/5V"))
    )
    (comp (ref "R63")
      (value "4K7")
      (footprint "eagle-import:0207_12")
      (libsource (lib "eagle-import") (part "R-EU_0207/12"))
    )
    (comp (ref "R64")
      (value "4K7")
      (footprint "eagle-import:0207_12")
      (libsource (lib "eagle-import") (part "R-EU_0207/12"))
    )
    (comp (ref "R65")
      (value "1K")
      (footprint "eagle-import:0207_12")
      (libsource (lib "eagle-import") (part "R-EU_0207/12"))
    )
    (comp (ref "R66")
      (value "470")
      (footprint "eagle-import:0207_12")
      (libsource (lib "eagle-import") (part "R-EU_0207/12"))
    )
    (comp (ref "R67")
      (value "470")
      (footprint "eagle-import:0207_12")
      (libsource (lib "eagle-import") (part "R-EU_0207/12"))
    )
    (comp (ref "R68")
      (value "33")
      (footprint "eagle-import:0207_12")
      (libsource (lib "eagle-import") (part "R-EU_0207/12"))
    )
    (comp (ref "R69")
      (value "100")
      (footprint "eagle-import:0207_5V")
      (libsource (lib "eagle-import") (part "R-EU_0207/5V"))
    )
    (comp (ref "R70")
      (value "100")
      (footprint "eagle-import:0207_5V")
      (libsource (lib "eagle-import") (part "R-EU_0207/5V"))
    )
    (comp (ref "R71")
      (value "3K3")
      (footprint "eagle-import:0207_5V")
      (libsource (lib "eagle-import") (part "R-EU_0207/5V"))
    )
    (comp (ref "R72")
      (value "10K")
      (footprint "eagle-import:0207_5V")
      (libsource (lib "eagle-import") (part "R-EU_0207/5V"))
    )
    (comp (ref "R73")
      (value "10K")
      (footprint "eagle-import:0207_5V")
      (libsource (lib "eagle-import") (part "R-EU_0207/5V"))
    )
    (comp (ref "R73_")
      (value "3K3")
      (footprint "eagle-import:0207_5V")
      (libsource (lib "eagle-import") (part "R-EU_0207/5V"))
    )
    (comp (ref "R74")
      (value "10K")
      (footprint "eagle-import:0207_5V")
      (libsource (lib "eagle-import") (part "R-EU_0207/5V"))
    )
    (comp (ref "R74_")
      (value "4K7")
      (footprint "eagle-import:0207_12")
      (libsource (lib "eagle-import") (part "R-EU_0207/12"))
    )
    (comp (ref "R75")
      (value "10K")
      (footprint "eagle-import:0207_12")
      (libsource (lib "eagle-import") (part "R-EU_0207/12"))
    )
    (comp (ref "R76")
      (value "150")
      (footprint "eagle-import:0207_5V")
      (libsource (lib "eagle-import") (part "R-EU_0207/5V"))
    )
    (comp (ref "R77")
      (value "75")
      (footprint "eagle-import:0207_5V")
      (libsource (lib "eagle-import") (part "R-EU_0207/5V"))
    )
    (comp (ref "TP1")
      (value "TPSQPAD1-13")
      (footprint "eagle-import:P1-13")
      (libsource (lib "eagle-import") (part "TPSQPAD1-13"))
    )
    (comp (ref "TP2")
      (value "TPSQPAD1-13")
      (footprint "eagle-import:P1-13")
      (libsource (lib "eagle-import") (part "TPSQPAD1-13"))
    )
    (comp (ref "TP3")
      (value "TPSQPAD1-13")
      (footprint "eagle-import:P1-13")
      (libsource (lib "eagle-import") (part "TPSQPAD1-13"))
    )
    (comp (ref "TP4")
      (value "TPSQPAD1-13")
      (footprint "eagle-import:P1-13")
      (libsource (lib "eagle-import") (part "TPSQPAD1-13"))
    )
    (comp (ref "TP5")
      (value "TPSQPAD1-13")
      (footprint "eagle-import:P1-13")
      (libsource (lib "eagle-import") (part "TPSQPAD1-13"))
    )
    (comp (ref "TP6")
      (value "TPSQPAD1-13")
      (footprint "eagle-import:P1-13")
      (libsource (lib "eagle-import") (part "TPSQPAD1-13"))
    )
    (comp (ref "TP7")
      (value "TPSQPAD1-13")
      (footprint "eagle-import:P1-13")
      (libsource (lib "eagle-import") (part "TPSQPAD1-13"))
    )
    (comp (ref "TP8")
      (value "TPSQPAD1-13")
      (footprint "eagle-import:P1-13")
      (libsource (lib "eagle-import") (part "TPSQPAD1-13"))
    )
    (comp (ref "TP9")
      (value "TPSQPAD1-13")
      (footprint "eagle-import:P1-13")
      (libsource (lib "eagle-import") (part "TPSQPAD1-13"))
    )
    (comp (ref "TP10")
      (value "TPSQPAD1-13")
      (footprint "eagle-import:P1-13")
      (libsource (lib "eagle-import") (part "TPSQPAD1-13"))
    )
    (comp (ref "U$1")
      (value "TK90_EDGE")
      (footprint "eagle-import:TK-EDGE")
      (libsource (lib "eagle-import") (part "TK90_EDGE"))
    )
    (comp (ref "X1")
      (value "POWER")
      (footprint "eagle-import:P2S")
      (libsource (lib "eagle-import") (part "JACKP2_S"))
    )
    (comp (ref "X2")
      (value "EAR")
      (footprint "eagle-import:P2S")
      (libsource (lib "eagle-import") (part "JACKP2_S"))
    )
    (comp (ref "X3")
      (value "MIC")
      (footprint "eagle-import:P2S")
      (libsource (lib "eagle-import") (part "JACKP2_S"))
    )
    (comp (ref "X4")
      (value "RCA")
      (footprint "eagle-import:DX1")
      (libsource (lib "eagle-import") (part "RCA2PINN1"))
    )
    (comp (ref "X5")
      (value "RCA")
      (footprint "eagle-import:DX1")
      (libsource (lib "eagle-import") (part "RCA2PINN1"))
    )
    (comp (ref "X6")
      (value "LED")
      (footprint "eagle-import:JP1")
      (libsource (lib "eagle-import") (part "JP1E"))
    )
    (comp (ref "X7")
      (value "JOYSTICK")
      (footprint "eagle-import:177-009-MALE")
      (libsource (lib "eagle-import") (part "M09?S.590"))
    )
    (comp (ref "X8")
      (value "JP1E")
      (footprint "eagle-import:JP1")
      (libsource (lib "eagle-import") (part "JP1E"))
    )
    (comp (ref "XTAL")
      (value "14.3044MHz")
      (footprint "eagle-import:HC49_S")
      (libsource (lib "eagle-import") (part "CRYSTALHC49S"))
    )
  )
  (nets
    (net (code "1") (name "+5V") (class "Default")
      (node (ref "C1") (pin "+") (pinfunction "+_+") (pintype "passive"))
      (node (ref "C12") (pin "2") (pinfunction "2_2") (pintype "passive"))
      (node (ref "C13") (pin "2") (pinfunction "2_2") (pintype "passive"))
      (node (ref "C14") (pin "2") (pinfunction "2_2") (pintype "passive"))
      (node (ref "C15") (pin "1") (pinfunction "1_1") (pintype "passive"))
      (node (ref "C16") (pin "1") (pinfunction "1_1") (pintype "passive"))
      (node (ref "C18") (pin "1") (pinfunction "1_1") (pintype "passive"))
      (node (ref "C19") (pin "1") (pinfunction "1_1") (pintype "passive"))
      (node (ref "C20") (pin "1") (pinfunction "1_1") (pintype "passive"))
      (node (ref "C21") (pin "1") (pinfunction "1_1") (pintype "passive"))
      (node (ref "C22") (pin "2") (pinfunction "2_2") (pintype "passive"))
      (node (ref "C24") (pin "2") (pinfunction "2_2") (pintype "passive"))
      (node (ref "C29") (pin "2") (pinfunction "2_2") (pintype "passive"))
      (node (ref "C31") (pin "2") (pinfunction "2_2") (pintype "passive"))
      (node (ref "C32") (pin "2") (pinfunction "2_2") (pintype "passive"))
      (node (ref "C33") (pin "2") (pinfunction "2_2") (pintype "passive"))
      (node (ref "D13") (pin "C") (pinfunction "K_C") (pintype "bidirectional"))
      (node (ref "D15") (pin "C") (pinfunction "K_C") (pintype "bidirectional"))
      (node (ref "D17") (pin "C") (pinfunction "K_C") (pintype "bidirectional"))
      (node (ref "IC1") (pin "11") (pinfunction "VCC_11") (pintype "power_in"))
      (node (ref "IC10") (pin "13") (pinfunction "A2_13") (pintype "input"))
      (node (ref "IC10") (pin "17") (pinfunction "A4_17") (pintype "input"))
      (node (ref "IC10") (pin "20") (pinfunction "VCC_20") (pintype "power_in"))
      (node (ref "IC11") (pin "20") (pinfunction "VCC_20") (pintype "power_in"))
      (node (ref "IC12") (pin "3") (pinfunction "CR_BIAS_3") (pintype "input"))
      (node (ref "IC13") (pin "9") (pinfunction "A7_9") (pintype "input"))
      (node (ref "IC14") (pin "9") (pinfunction "A7_9") (pintype "input"))
      (node (ref "IC15") (pin "9") (pinfunction "A7_9") (pintype "input"))
      (node (ref "IC16") (pin "9") (pinfunction "A7_9") (pintype "input"))
      (node (ref "IC17") (pin "9") (pinfunction "A7_9") (pintype "input"))
      (node (ref "IC18") (pin "9") (pinfunction "A7_9") (pintype "input"))
      (node (ref "IC19") (pin "9") (pinfunction "A7_9") (pintype "input"))
      (node (ref "IC2") (pin "1") (pinfunction "VPP_1") (pintype "input"))
      (node (ref "IC2") (pin "28") (pinfunction "VCC_28") (pintype "power_in"))
      (node (ref "IC20") (pin "9") (pinfunction "A7_9") (pintype "input"))
      (node (ref "IC21") (pin "9") (pinfunction "VCC_9") (pintype "power_in"))
      (node (ref "IC22") (pin "9") (pinfunction "VCC_9") (pintype "power_in"))
      (node (ref "IC23") (pin "9") (pinfunction "VCC_9") (pintype "power_in"))
      (node (ref "IC24") (pin "9") (pinfunction "VCC_9") (pintype "power_in"))
      (node (ref "IC25") (pin "14") (pinfunction "VCC_14") (pintype "power_in"))
      (node (ref "IC26") (pin "1") (pinfunction "I0_1") (pintype "input"))
      (node (ref "IC26") (pin "14") (pinfunction "VCC_14") (pintype "power_in"))
      (node (ref "IC27") (pin "14") (pinfunction "VCC_14") (pintype "power_in"))
      (node (ref "IC28") (pin "14") (pinfunction "VCC_14") (pintype "power_in"))
      (node (ref "IC29") (pin "OUT") (pinfunction "OUT_OUT") (pintype "passive"))
      (node (ref "IC3") (pin "40") (pinfunction "VCC_40") (pintype "power_in"))
      (node (ref "IC4") (pin "1") (pinfunction "CLR_1") (pintype "input"))
      (node (ref "IC4") (pin "10") (pinfunction "PRE_10") (pintype "input"))
      (node (ref "IC4") (pin "13") (pinfunction "CLR_13") (pintype "input"))
      (node (ref "IC4") (pin "14") (pinfunction "VCC_14") (pintype "power_in"))
      (node (ref "IC4") (pin "2") (pinfunction "D_2") (pintype "input"))
      (node (ref "IC4") (pin "3") (pinfunction "CLK_3") (pintype "input"))
      (node (ref "IC4") (pin "4") (pinfunction "PRE_4") (pintype "input"))
      (node (ref "IC5") (pin "1") (pinfunction "CLR_1") (pintype "input"))
      (node (ref "IC5") (pin "10") (pinfunction "PRE_10") (pintype "input"))
      (node (ref "IC5") (pin "13") (pinfunction "CLR_13") (pintype "input"))
      (node (ref "IC5") (pin "14") (pinfunction "VCC_14") (pintype "power_in"))
      (node (ref "IC5") (pin "4") (pinfunction "PRE_4") (pintype "input"))
      (node (ref "IC6") (pin "16") (pinfunction "VCC_16") (pintype "power_in"))
      (node (ref "IC7") (pin "16") (pinfunction "VCC_16") (pintype "power_in"))
      (node (ref "IC8") (pin "16") (pinfunction "VCC_16") (pintype "power_in"))
      (node (ref "IC9") (pin "16") (pinfunction "VCC_16") (pintype "power_in"))
      (node (ref "J2") (pin "3") (pinfunction "3_3") (pintype "passive"))
      (node (ref "J9") (pin "3") (pinfunction "3_3") (pintype "passive"))
      (node (ref "Q1") (pin "3") (pinfunction "C_3") (pintype "passive"))
      (node (ref "R17") (pin "2") (pinfunction "2_2") (pintype "passive"))
      (node (ref "R18") (pin "2") (pinfunction "2_2") (pintype "passive"))
      (node (ref "R19") (pin "2") (pinfunction "2_2") (pintype "passive"))
      (node (ref "R20") (pin "2") (pinfunction "2_2") (pintype "passive"))
      (node (ref "R21") (pin "2") (pinfunction "2_2") (pintype "passive"))
      (node (ref "R22") (pin "2") (pinfunction "2_2") (pintype "passive"))
      (node (ref "R23") (pin "2") (pinfunction "2_2") (pintype "passive"))
      (node (ref "R24") (pin "2") (pinfunction "2_2") (pintype "passive"))
      (node (ref "R29") (pin "2") (pinfunction "2_2") (pintype "passive"))
      (node (ref "R30") (pin "1") (pinfunction "1_1") (pintype "passive"))
      (node (ref "R31") (pin "1") (pinfunction "1_1") (pintype "passive"))
      (node (ref "R32") (pin "1") (pinfunction "1_1") (pintype "passive"))
      (node (ref "R35") (pin "1") (pinfunction "1_1") (pintype "passive"))
      (node (ref "R36") (pin "1") (pinfunction "1_1") (pintype "passive"))
      (node (ref "R37") (pin "1") (pinfunction "1_1") (pintype "passive"))
      (node (ref "R38") (pin "1") (pinfunction "1_1") (pintype "passive"))
      (node (ref "R39") (pin "1") (pinfunction "1_1") (pintype "passive"))
      (node (ref "R40") (pin "2") (pinfunction "2_2") (pintype "passive"))
      (node (ref "R43") (pin "2") (pinfunction "2_2") (pintype "passive"))
      (node (ref "R48") (pin "2") (pinfunction "2_2") (pintype "passive"))
      (node (ref "R51") (pin "2") (pinfunction "2_2") (pintype "passive"))
      (node (ref "R54") (pin "1") (pinfunction "1_1") (pintype "passive"))
      (node (ref "R74_") (pin "2") (pinfunction "2_2") (pintype "passive"))
      (node (ref "U$1") (pin "3A") (pinfunction "EDGE_3A") (pintype "bidirectional"))
      (node (ref "X6") (pin "1") (pinfunction "1_1") (pintype "passive"))
    )
    (net (code "2") (name "+12V") (class "Default")
      (node (ref "C43") (pin "2") (pinfunction "2_2") (pintype "passive"))
      (node (ref "C53") (pin "+") (pinfunction "+_+") (pintype "passive"))
      (node (ref "D24") (pin "C") (pinfunction "K_C") (pintype "bidirectional"))
      (node (ref "IC11") (pin "5") (pinfunction "+12V_5") (pintype "power_in"))
      (node (ref "IC12") (pin "14") (pinfunction "RFVCC_14") (pintype "power_in"))
      (node (ref "IC12") (pin "16") (pinfunction "CRVCC_16") (pintype "power_in"))
      (node (ref "Q8") (pin "3") (pinfunction "C_3") (pintype "passive"))
      (node (ref "R68") (pin "1") (pinfunction "1_1") (pintype "passive"))
      (node (ref "U$1") (pin "22B") (pinfunction "EDGE_22B") (pintype "bidirectional"))
    )
    (net (code "3") (name "-5V") (class "Default")
      (node (ref "C50") (pin "1") (pinfunction "1_1") (pintype "passive"))
      (node (ref "D21") (pin "A") (pinfunction "A_A") (pintype "bidirectional"))
      (node (ref "J3") (pin "1") (pinfunction "1_1") (pintype "passive"))
      (node (ref "R67") (pin "1") (pinfunction "1_1") (pintype "passive"))
      (node (ref "U$1") (pin "20B") (pinfunction "EDGE_20B") (pintype "bidirectional"))
    )
    (net (code "4") (name "/+12V_UNREG") (class "Default")
      (node (ref "C48") (pin "1") (pinfunction "1_1") (pintype "passive"))
      (node (ref "C51") (pin "1") (pinfunction "1_1") (pintype "passive"))
      (node (ref "Q5") (pin "E") (pinfunction "E_E") (pintype "passive"))
      (node (ref "Q6") (pin "E") (pinfunction "E_E") (pintype "passive"))
      (node (ref "U$1") (pin "23B") (pinfunction "EDGE_23B") (pintype "bidirectional"))
    )
    (net (code "5") (name "/A0") (class "Default")
      (node (ref "IC1") (pin "30") (pinfunction "A0_30") (pintype "output"))
      (node (ref "IC2") (pin "10") (pinfunction "A0_10") (pintype "input"))
      (node (ref "IC7") (pin "3") (pinfunction "1B_3") (pintype "input"))
      (node (ref "IC8") (pin "3") (pinfunction "1B_3") (pintype "input"))
      (node (ref "Q1") (pin "2") (pinfunction "B_2") (pintype "passive"))
      (node (ref "U$1") (pin "9A") (pinfunction "EDGE_9A") (pintype "bidirectional"))
    )
    (net (code "6") (name "/A1") (class "Default")
      (node (ref "IC1") (pin "31") (pinfunction "A1_31") (pintype "output"))
      (node (ref "IC2") (pin "9") (pinfunction "A1_9") (pintype "input"))
      (node (ref "IC7") (pin "6") (pinfunction "2B_6") (pintype "input"))
      (node (ref "IC8") (pin "6") (pinfunction "2B_6") (pintype "input"))
      (node (ref "U$1") (pin "10A") (pinfunction "EDGE_10A") (pintype "bidirectional"))
    )
    (net (code "7") (name "/A2") (class "Default")
      (node (ref "IC1") (pin "32") (pinfunction "A2_32") (pintype "output"))
      (node (ref "IC2") (pin "8") (pinfunction "A2_8") (pintype "input"))
      (node (ref "IC7") (pin "13") (pinfunction "4B_13") (pintype "input"))
      (node (ref "IC8") (pin "13") (pinfunction "4B_13") (pintype "input"))
      (node (ref "U$1") (pin "11A") (pinfunction "EDGE_11A") (pintype "bidirectional"))
    )
    (net (code "8") (name "/A3") (class "Default")
      (node (ref "IC1") (pin "33") (pinfunction "A3_33") (pintype "output"))
      (node (ref "IC2") (pin "7") (pinfunction "A3_7") (pintype "input"))
      (node (ref "IC7") (pin "10") (pinfunction "3B_10") (pintype "input"))
      (node (ref "IC8") (pin "10") (pinfunction "3B_10") (pintype "input"))
      (node (ref "U$1") (pin "12A") (pinfunction "EDGE_12A") (pintype "bidirectional"))
    )
    (net (code "9") (name "/A4") (class "Default")
      (node (ref "IC1") (pin "34") (pinfunction "A4_34") (pintype "output"))
      (node (ref "IC2") (pin "6") (pinfunction "A4_6") (pintype "input"))
      (node (ref "IC6") (pin "6") (pinfunction "2B_6") (pintype "input"))
      (node (ref "IC9") (pin "6") (pinfunction "2B_6") (pintype "input"))
      (node (ref "U$1") (pin "24A") (pinfunction "EDGE_24A") (pintype "bidirectional"))
    )
    (net (code "10") (name "/A5") (class "Default")
      (node (ref "IC1") (pin "35") (pinfunction "A5_35") (pintype "output"))
      (node (ref "IC2") (pin "5") (pinfunction "A5_5") (pintype "input"))
      (node (ref "IC6") (pin "13") (pinfunction "4B_13") (pintype "input"))
      (node (ref "IC9") (pin "13") (pinfunction "4B_13") (pintype "input"))
      (node (ref "U$1") (pin "23A") (pinfunction "EDGE_23A") (pintype "bidirectional"))
    )
    (net (code "11") (name "/A6") (class "Default")
      (node (ref "IC1") (pin "36") (pinfunction "A6_36") (pintype "output"))
      (node (ref "IC2") (pin "4") (pinfunction "A6_4") (pintype "input"))
      (node (ref "IC21") (pin "14") (pinfunction "A0_14") (pintype "input"))
      (node (ref "IC22") (pin "14") (pinfunction "A0_14") (pintype "input"))
      (node (ref "IC23") (pin "14") (pinfunction "A0_14") (pintype "input"))
      (node (ref "IC24") (pin "14") (pinfunction "A0_14") (pintype "input"))
      (node (ref "IC5") (pin "12") (pinfunction "D_12") (pintype "input"))
      (node (ref "IC9") (pin "10") (pinfunction "3B_10") (pintype "input"))
      (node (ref "U$1") (pin "22A") (pinfunction "EDGE_22A") (pintype "bidirectional"))
    )
    (net (code "12") (name "/A7") (class "Default")
      (node (ref "IC1") (pin "37") (pinfunction "A7_37") (pintype "output"))
      (node (ref "IC2") (pin "3") (pinfunction "A7_3") (pintype "input"))
      (node (ref "IC26") (pin "12") (pinfunction "I0_12") (pintype "input"))
      (node (ref "IC8") (pin "2") (pinfunction "1A_2") (pintype "input"))
      (node (ref "U$1") (pin "21A") (pinfunction "EDGE_21A") (pintype "bidirectional"))
    )
    (net (code "13") (name "/A7'") (class "Default")
      (node (ref "IC21") (pin "10") (pinfunction "A7_10") (pintype "input"))
      (node (ref "IC22") (pin "10") (pinfunction "A7_10") (pintype "input"))
      (node (ref "IC23") (pin "10") (pinfunction "A7_10") (pintype "input"))
      (node (ref "IC24") (pin "10") (pinfunction "A7_10") (pintype "input"))
      (node (ref "IC26") (pin "8") (pinfunction "O_8") (pintype "output"))
    )
    (net (code "14") (name "/A8") (class "Default")
      (node (ref "D2") (pin "C") (pinfunction "K_C") (pintype "bidirectional"))
      (node (ref "IC1") (pin "38") (pinfunction "A8_38") (pintype "output"))
      (node (ref "IC2") (pin "25") (pinfunction "A8_25") (pintype "input"))
      (node (ref "IC7") (pin "5") (pinfunction "2A_5") (pintype "input"))
      (node (ref "IC8") (pin "5") (pinfunction "2A_5") (pintype "input"))
      (node (ref "U$1") (pin "26B") (pinfunction "EDGE_26B") (pintype "bidirectional"))
    )
    (net (code "15") (name "/A8-1") (class "Default")
      (node (ref "IC21") (pin "7") (pinfunction "A5_7") (pintype "input"))
      (node (ref "IC22") (pin "7") (pinfunction "A5_7") (pintype "input"))
      (node (ref "IC23") (pin "7") (pinfunction "A5_7") (pintype "input"))
      (node (ref "IC24") (pin "7") (pinfunction "A5_7") (pintype "input"))
      (node (ref "IC7") (pin "7") (pinfunction "2Y_7") (pintype "output"))
    )
    (net (code "16") (name "/A9") (class "Default")
      (node (ref "D3") (pin "C") (pinfunction "K_C") (pintype "bidirectional"))
      (node (ref "IC1") (pin "39") (pinfunction "A9_39") (pintype "output"))
      (node (ref "IC2") (pin "24") (pinfunction "A9_24") (pintype "input"))
      (node (ref "IC7") (pin "14") (pinfunction "4A_14") (pintype "input"))
      (node (ref "IC8") (pin "14") (pinfunction "4A_14") (pintype "input"))
      (node (ref "U$1") (pin "27A") (pinfunction "EDGE_27A") (pintype "bidirectional"))
    )
    (net (code "17") (name "/A9-2") (class "Default")
      (node (ref "IC21") (pin "8") (pinfunction "A4_8") (pintype "input"))
      (node (ref "IC22") (pin "8") (pinfunction "A4_8") (pintype "input"))
      (node (ref "IC23") (pin "8") (pinfunction "A4_8") (pintype "input"))
      (node (ref "IC24") (pin "8") (pinfunction "A4_8") (pintype "input"))
      (node (ref "IC7") (pin "12") (pinfunction "4Y_12") (pintype "output"))
    )
    (net (code "18") (name "/A10") (class "Default")
      (node (ref "D4") (pin "C") (pinfunction "K_C") (pintype "bidirectional"))
      (node (ref "IC1") (pin "40") (pinfunction "A10_40") (pintype "output"))
      (node (ref "IC2") (pin "21") (pinfunction "A10_21") (pintype "input"))
      (node (ref "IC7") (pin "11") (pinfunction "3A_11") (pintype "input"))
      (node (ref "IC8") (pin "11") (pinfunction "3A_11") (pintype "input"))
      (node (ref "U$1") (pin "27B") (pinfunction "EDGE_27B") (pintype "bidirectional"))
    )
    (net (code "19") (name "/A10-3") (class "Default")
      (node (ref "IC21") (pin "11") (pinfunction "A3_11") (pintype "input"))
      (node (ref "IC22") (pin "11") (pinfunction "A3_11") (pintype "input"))
      (node (ref "IC23") (pin "11") (pinfunction "A3_11") (pintype "input"))
      (node (ref "IC24") (pin "11") (pinfunction "A3_11") (pintype "input"))
      (node (ref "IC7") (pin "9") (pinfunction "3Y_9") (pintype "output"))
    )
    (net (code "20") (name "/A11") (class "Default")
      (node (ref "D5") (pin "C") (pinfunction "K_C") (pintype "bidirectional"))
      (node (ref "IC1") (pin "1") (pinfunction "A11_1") (pintype "output"))
      (node (ref "IC2") (pin "23") (pinfunction "A11_23") (pintype "input"))
      (node (ref "IC6") (pin "5") (pinfunction "2A_5") (pintype "input"))
      (node (ref "IC9") (pin "5") (pinfunction "2A_5") (pintype "input"))
      (node (ref "U$1") (pin "28A") (pinfunction "EDGE_28A") (pintype "bidirectional"))
    )
    (net (code "21") (name "/A11-4") (class "Default")
      (node (ref "IC21") (pin "12") (pinfunction "A2_12") (pintype "input"))
      (node (ref "IC22") (pin "12") (pinfunction "A2_12") (pintype "input"))
      (node (ref "IC23") (pin "12") (pinfunction "A2_12") (pintype "input"))
      (node (ref "IC24") (pin "12") (pinfunction "A2_12") (pintype "input"))
      (node (ref "IC6") (pin "7") (pinfunction "2Y_7") (pintype "output"))
    )
    (net (code "22") (name "/A12") (class "Default")
      (node (ref "D6") (pin "C") (pinfunction "K_C") (pintype "bidirectional"))
      (node (ref "IC1") (pin "2") (pinfunction "A12_2") (pintype "output"))
      (node (ref "IC2") (pin "2") (pinfunction "A12_2") (pintype "input"))
      (node (ref "IC6") (pin "14") (pinfunction "4A_14") (pintype "input"))
      (node (ref "IC9") (pin "14") (pinfunction "4A_14") (pintype "input"))
      (node (ref "U$1") (pin "2A") (pinfunction "EDGE_2A") (pintype "bidirectional"))
    )
    (net (code "23") (name "/A12-5") (class "Default")
      (node (ref "IC21") (pin "13") (pinfunction "A1_13") (pintype "input"))
      (node (ref "IC22") (pin "13") (pinfunction "A1_13") (pintype "input"))
      (node (ref "IC23") (pin "13") (pinfunction "A1_13") (pintype "input"))
      (node (ref "IC24") (pin "13") (pinfunction "A1_13") (pintype "input"))
      (node (ref "IC6") (pin "12") (pinfunction "4Y_12") (pintype "output"))
    )
    (net (code "24") (name "/A13") (class "Default")
      (node (ref "D7") (pin "C") (pinfunction "K_C") (pintype "bidirectional"))
      (node (ref "IC1") (pin "3") (pinfunction "A13_3") (pintype "output"))
      (node (ref "IC2") (pin "26") (pinfunction "A13_26") (pintype "input"))
      (node (ref "IC7") (pin "2") (pinfunction "1A_2") (pintype "input"))
      (node (ref "IC9") (pin "11") (pinfunction "3A_11") (pintype "input"))
      (node (ref "U$1") (pin "2B") (pinfunction "EDGE_2B") (pintype "bidirectional"))
    )
    (net (code "25") (name "/A13-0") (class "Default")
      (node (ref "IC21") (pin "6") (pinfunction "A6_6") (pintype "input"))
      (node (ref "IC22") (pin "6") (pinfunction "A6_6") (pintype "input"))
      (node (ref "IC23") (pin "6") (pinfunction "A6_6") (pintype "input"))
      (node (ref "IC24") (pin "6") (pinfunction "A6_6") (pintype "input"))
      (node (ref "IC7") (pin "4") (pinfunction "1Y_4") (pintype "output"))
    )
    (net (code "26") (name "/A14") (class "Default")
      (node (ref "D12") (pin "A") (pinfunction "A_A") (pintype "bidirectional"))
      (node (ref "D8") (pin "C") (pinfunction "K_C") (pintype "bidirectional"))
      (node (ref "IC1") (pin "4") (pinfunction "A14_4") (pintype "output"))
      (node (ref "IC25") (pin "4") (pinfunction "I0_4") (pintype "input"))
      (node (ref "IC27") (pin "12") (pinfunction "I0_12") (pintype "input"))
      (node (ref "IC28") (pin "1") (pinfunction "I_1") (pintype "input"))
      (node (ref "IC3") (pin "37") (pinfunction "A14_37") (pintype "input"))
      (node (ref "U$1") (pin "1A") (pinfunction "EDGE_1A") (pintype "bidirectional"))
    )
    (net (code "27") (name "/A15") (class "Default")
      (node (ref "D11") (pin "A") (pinfunction "A_A") (pintype "bidirectional"))
      (node (ref "D9") (pin "C") (pinfunction "K_C") (pintype "bidirectional"))
      (node (ref "IC1") (pin "5") (pinfunction "A15_5") (pintype "output"))
      (node (ref "IC25") (pin "13") (pinfunction "I1_13") (pintype "input"))
      (node (ref "IC27") (pin "13") (pinfunction "I1_13") (pintype "input"))
      (node (ref "IC3") (pin "38") (pinfunction "A15_38") (pintype "input"))
      (node (ref "U$1") (pin "1B") (pinfunction "EDGE_1B") (pintype "bidirectional"))
    )
    (net (code "28") (name "/AA0") (class "Default")
      (node (ref "IC13") (pin "5") (pinfunction "A0_5") (pintype "input"))
      (node (ref "IC14") (pin "5") (pinfunction "A0_5") (pintype "input"))
      (node (ref "IC15") (pin "5") (pinfunction "A0_5") (pintype "input"))
      (node (ref "IC16") (pin "5") (pinfunction "A0_5") (pintype "input"))
      (node (ref "IC17") (pin "5") (pinfunction "A0_5") (pintype "input"))
      (node (ref "IC18") (pin "5") (pinfunction "A0_5") (pintype "input"))
      (node (ref "IC19") (pin "5") (pinfunction "A0_5") (pintype "input"))
      (node (ref "IC20") (pin "5") (pinfunction "A0_5") (pintype "input"))
      (node (ref "IC3") (pin "9") (pinfunction "A0_9") (pintype "output"))
      (node (ref "R9") (pin "1") (pinfunction "1_1") (pintype "passive"))
    )
    (net (code "29") (name "/AA1") (class "Default")
      (node (ref "IC13") (pin "7") (pinfunction "A1_7") (pintype "input"))
      (node (ref "IC14") (pin "7") (pinfunction "A1_7") (pintype "input"))
      (node (ref "IC15") (pin "7") (pinfunction "A1_7") (pintype "input"))
      (node (ref "IC16") (pin "7") (pinfunction "A1_7") (pintype "input"))
      (node (ref "IC17") (pin "7") (pinfunction "A1_7") (pintype "input"))
      (node (ref "IC18") (pin "7") (pinfunction "A1_7") (pintype "input"))
      (node (ref "IC19") (pin "7") (pinfunction "A1_7") (pintype "input"))
      (node (ref "IC20") (pin "7") (pinfunction "A1_7") (pintype "input"))
      (node (ref "IC3") (pin "7") (pinfunction "A1_7") (pintype "output"))
      (node (ref "R11") (pin "1") (pinfunction "1_1") (pintype "passive"))
    )
    (net (code "30") (name "/AA2") (class "Default")
      (node (ref "IC13") (pin "6") (pinfunction "A2_6") (pintype "input"))
      (node (ref "IC14") (pin "6") (pinfunction "A2_6") (pintype "input"))
      (node (ref "IC15") (pin "6") (pinfunction "A2_6") (pintype "input"))
      (node (ref "IC16") (pin "6") (pinfunction "A2_6") (pintype "input"))
      (node (ref "IC17") (pin "6") (pinfunction "A2_6") (pintype "input"))
      (node (ref "IC18") (pin "6") (pinfunction "A2_6") (pintype "input"))
      (node (ref "IC19") (pin "6") (pinfunction "A2_6") (pintype "input"))
      (node (ref "IC20") (pin "6") (pinfunction "A2_6") (pintype "input"))
      (node (ref "IC3") (pin "8") (pinfunction "A2_8") (pintype "output"))
      (node (ref "R10") (pin "1") (pinfunction "1_1") (pintype "passive"))
    )
    (net (code "31") (name "/AA3") (class "Default")
      (node (ref "IC13") (pin "12") (pinfunction "A3_12") (pintype "input"))
      (node (ref "IC14") (pin "12") (pinfunction "A3_12") (pintype "input"))
      (node (ref "IC15") (pin "12") (pinfunction "A3_12") (pintype "input"))
      (node (ref "IC16") (pin "12") (pinfunction "A3_12") (pintype "input"))
      (node (ref "IC17") (pin "12") (pinfunction "A3_12") (pintype "input"))
      (node (ref "IC18") (pin "12") (pinfunction "A3_12") (pintype "input"))
      (node (ref "IC19") (pin "12") (pinfunction "A3_12") (pintype "input"))
      (node (ref "IC20") (pin "12") (pinfunction "A3_12") (pintype "input"))
      (node (ref "IC3") (pin "4") (pinfunction "A3_4") (pintype "output"))
      (node (ref "R14") (pin "1") (pinfunction "1_1") (pintype "passive"))
    )
    (net (code "32") (name "/AA4") (class "Default")
      (node (ref "IC13") (pin "11") (pinfunction "A4_11") (pintype "input"))
      (node (ref "IC14") (pin "11") (pinfunction "A4_11") (pintype "input"))
      (node (ref "IC15") (pin "11") (pinfunction "A4_11") (pintype "input"))
      (node (ref "IC16") (pin "11") (pinfunction "A4_11") (pintype "input"))
      (node (ref "IC17") (pin "11") (pinfunction "A4_11") (pintype "input"))
      (node (ref "IC18") (pin "11") (pinfunction "A4_11") (pintype "input"))
      (node (ref "IC19") (pin "11") (pinfunction "A4_11") (pintype "input"))
      (node (ref "IC20") (pin "11") (pinfunction "A4_11") (pintype "input"))
      (node (ref "IC3") (pin "5") (pinfunction "A4_5") (pintype "output"))
      (node (ref "R13") (pin "1") (pinfunction "1_1") (pintype "passive"))
    )
    (net (code "33") (name "/AA5") (class "Default")
      (node (ref "IC13") (pin "10") (pinfunction "A5_10") (pintype "input"))
      (node (ref "IC14") (pin "10") (pinfunction "A5_10") (pintype "input"))
      (node (ref "IC15") (pin "10") (pinfunction "A5_10") (pintype "input"))
      (node (ref "IC16") (pin "10") (pinfunction "A5_10") (pintype "input"))
      (node (ref "IC17") (pin "10") (pinfunction "A5_10") (pintype "input"))
      (node (ref "IC18") (pin "10") (pinfunction "A5_10") (pintype "input"))
      (node (ref "IC19") (pin "10") (pinfunction "A5_10") (pintype "input"))
      (node (ref "IC20") (pin "10") (pinfunction "A5_10") (pintype "input"))
      (node (ref "IC3") (pin "6") (pinfunction "A5_6") (pintype "output"))
      (node (ref "R12") (pin "1") (pinfunction "1_1") (pintype "passive"))
    )
    (net (code "34") (name "/AA6") (class "Default")
      (node (ref "IC13") (pin "13") (pinfunction "A6_13") (pintype "input"))
      (node (ref "IC14") (pin "13") (pinfunction "A6_13") (pintype "input"))
      (node (ref "IC15") (pin "13") (pinfunction "A6_13") (pintype "input"))
      (node (ref "IC16") (pin "13") (pinfunction "A6_13") (pintype "input"))
      (node (ref "IC17") (pin "13") (pinfunction "A6_13") (pintype "input"))
      (node (ref "IC18") (pin "13") (pinfunction "A6_13") (pintype "input"))
      (node (ref "IC19") (pin "13") (pinfunction "A6_13") (pintype "input"))
      (node (ref "IC20") (pin "13") (pinfunction "A6_13") (pintype "input"))
      (node (ref "IC3") (pin "3") (pinfunction "A6_3") (pintype "output"))
      (node (ref "R15") (pin "1") (pinfunction "1_1") (pintype "passive"))
    )
    (net (code "35") (name "/CARRIER") (class "Default")
      (node (ref "C47") (pin "1") (pinfunction "1_1") (pintype "passive"))
      (node (ref "D17") (pin "A") (pinfunction "A_A") (pintype "bidirectional"))
      (node (ref "D18") (pin "C") (pinfunction "K_C") (pintype "bidirectional"))
      (node (ref "IC3") (pin "39") (pinfunction "CARRIER_39") (pintype "output"))
      (node (ref "R64") (pin "2") (pinfunction "2_2") (pintype "passive"))
      (node (ref "R71") (pin "2") (pinfunction "2_2") (pintype "passive"))
    )
    (net (code "36") (name "/CLK") (class "Default")
      (node (ref "C9") (pin "2") (pinfunction "2_2") (pintype "passive"))
      (node (ref "IC3") (pin "36") (pinfunction "CKOUT_36") (pintype "output"))
      (node (ref "R49") (pin "2") (pinfunction "2_2") (pintype "passive"))
      (node (ref "R51") (pin "1") (pinfunction "1_1") (pintype "passive"))
      (node (ref "U$1") (pin "8A") (pinfunction "EDGE_8A") (pintype "bidirectional"))
    )
    (net (code "37") (name "/D0") (class "Default")
      (node (ref "IC1") (pin "14") (pinfunction "D0_14") (pintype "bidirectional"))
      (node (ref "IC10") (pin "18") (pinfunction "Y1_18") (pintype "tri_state"))
      (node (ref "IC2") (pin "11") (pinfunction "O0_11") (pintype "tri_state"))
      (node (ref "IC21") (pin "2") (pinfunction "I/O1_2") (pintype "bidirectional"))
      (node (ref "IC23") (pin "2") (pinfunction "I/O1_2") (pintype "bidirectional"))
      (node (ref "R1") (pin "2") (pinfunction "2_2") (pintype "passive"))
      (node (ref "R17") (pin "1") (pinfunction "1_1") (pintype "passive"))
      (node (ref "U$1") (pin "6B") (pinfunction "EDGE_6B") (pintype "bidirectional"))
    )
    (net (code "38") (name "/D0'") (class "Default")
      (node (ref "IC20") (pin "14") (pinfunction "DO_14") (pintype "bidirectional"))
      (node (ref "IC20") (pin "2") (pinfunction "DI_2") (pintype "bidirectional"))
      (node (ref "IC3") (pin "25") (pinfunction "D0_25") (pintype "bidirectional"))
      (node (ref "R1") (pin "1") (pinfunction "1_1") (pintype "passive"))
    )
    (net (code "39") (name "/D1") (class "Default")
      (node (ref "IC1") (pin "15") (pinfunction "D1_15") (pintype "bidirectional"))
      (node (ref "IC10") (pin "16") (pinfunction "Y2_16") (pintype "tri_state"))
      (node (ref "IC2") (pin "12") (pinfunction "O1_12") (pintype "tri_state"))
      (node (ref "IC21") (pin "3") (pinfunction "I/O2_3") (pintype "bidirectional"))
      (node (ref "IC23") (pin "3") (pinfunction "I/O2_3") (pintype "bidirectional"))
      (node (ref "R18") (pin "1") (pinfunction "1_1") (pintype "passive"))
      (node (ref "R2") (pin "2") (pinfunction "2_2") (pintype "passive"))
      (node (ref "U$1") (pin "7B") (pinfunction "EDGE_7B") (pintype "bidirectional"))
    )
    (net (code "40") (name "/D1'") (class "Default")
      (node (ref "IC19") (pin "14") (pinfunction "DO_14") (pintype "bidirectional"))
      (node (ref "IC19") (pin "2") (pinfunction "DI_2") (pintype "bidirectional"))
      (node (ref "IC3") (pin "26") (pinfunction "D1_26") (pintype "bidirectional"))
      (node (ref "R2") (pin "1") (pinfunction "1_1") (pintype "passive"))
    )
    (net (code "41") (name "/D2") (class "Default")
      (node (ref "IC1") (pin "12") (pinfunction "D2_12") (pintype "bidirectional"))
      (node (ref "IC10") (pin "14") (pinfunction "Y3_14") (pintype "tri_state"))
      (node (ref "IC2") (pin "13") (pinfunction "O2_13") (pintype "tri_state"))
      (node (ref "IC21") (pin "15") (pinfunction "I/O3_15") (pintype "bidirectional"))
      (node (ref "IC23") (pin "15") (pinfunction "I/O3_15") (pintype "bidirectional"))
      (node (ref "R19") (pin "1") (pinfunction "1_1") (pintype "passive"))
      (node (ref "R3") (pin "2") (pinfunction "2_2") (pintype "passive"))
      (node (ref "U$1") (pin "8B") (pinfunction "EDGE_8B") (pintype "bidirectional"))
    )
    (net (code "42") (name "/D2'") (class "Default")
      (node (ref "IC18") (pin "14") (pinfunction "DO_14") (pintype "bidirectional"))
      (node (ref "IC18") (pin "2") (pinfunction "DI_2") (pintype "bidirectional"))
      (node (ref "IC3") (pin "27") (pinfunction "D2_27") (pintype "bidirectional"))
      (node (ref "R3") (pin "1") (pinfunction "1_1") (pintype "passive"))
    )
    (net (code "43") (name "/D3") (class "Default")
      (node (ref "IC1") (pin "8") (pinfunction "D3_8") (pintype "bidirectional"))
      (node (ref "IC10") (pin "12") (pinfunction "Y4_12") (pintype "tri_state"))
      (node (ref "IC2") (pin "15") (pinfunction "O3_15") (pintype "tri_state"))
      (node (ref "IC21") (pin "17") (pinfunction "I/O4_17") (pintype "bidirectional"))
      (node (ref "IC23") (pin "17") (pinfunction "I/O4_17") (pintype "bidirectional"))
      (node (ref "R20") (pin "1") (pinfunction "1_1") (pintype "passive"))
      (node (ref "R4") (pin "2") (pinfunction "2_2") (pintype "passive"))
      (node (ref "U$1") (pin "11B") (pinfunction "EDGE_11B") (pintype "bidirectional"))
    )
    (net (code "44") (name "/D3'") (class "Default")
      (node (ref "IC17") (pin "14") (pinfunction "DO_14") (pintype "bidirectional"))
      (node (ref "IC17") (pin "2") (pinfunction "DI_2") (pintype "bidirectional"))
      (node (ref "IC3") (pin "28") (pinfunction "D3_28") (pintype "bidirectional"))
      (node (ref "R4") (pin "1") (pinfunction "1_1") (pintype "passive"))
    )
    (net (code "45") (name "/D4") (class "Default")
      (node (ref "IC1") (pin "7") (pinfunction "D4_7") (pintype "bidirectional"))
      (node (ref "IC10") (pin "9") (pinfunction "Y1_9") (pintype "tri_state"))
      (node (ref "IC2") (pin "16") (pinfunction "O4_16") (pintype "tri_state"))
      (node (ref "IC22") (pin "2") (pinfunction "I/O1_2") (pintype "bidirectional"))
      (node (ref "IC24") (pin "2") (pinfunction "I/O1_2") (pintype "bidirectional"))
      (node (ref "R21") (pin "1") (pinfunction "1_1") (pintype "passive"))
      (node (ref "R5") (pin "2") (pinfunction "2_2") (pintype "passive"))
      (node (ref "U$1") (pin "12B") (pinfunction "EDGE_12B") (pintype "bidirectional"))
    )
    (net (code "46") (name "/D4'") (class "Default")
      (node (ref "IC16") (pin "14") (pinfunction "DO_14") (pintype "bidirectional"))
      (node (ref "IC16") (pin "2") (pinfunction "DI_2") (pintype "bidirectional"))
      (node (ref "IC3") (pin "29") (pinfunction "D4_29") (pintype "bidirectional"))
      (node (ref "R5") (pin "1") (pinfunction "1_1") (pintype "passive"))
    )
    (net (code "47") (name "/D5") (class "Default")
      (node (ref "IC1") (pin "9") (pinfunction "D5_9") (pintype "bidirectional"))
      (node (ref "IC10") (pin "7") (pinfunction "Y2_7") (pintype "tri_state"))
      (node (ref "IC2") (pin "17") (pinfunction "O5_17") (pintype "tri_state"))
      (node (ref "IC22") (pin "3") (pinfunction "I/O2_3") (pintype "bidirectional"))
      (node (ref "IC24") (pin "3") (pinfunction "I/O2_3") (pintype "bidirectional"))
      (node (ref "R22") (pin "1") (pinfunction "1_1") (pintype "passive"))
      (node (ref "R6") (pin "2") (pinfunction "2_2") (pintype "passive"))
      (node (ref "U$1") (pin "10B") (pinfunction "EDGE_10B") (pintype "bidirectional"))
    )
    (net (code "48") (name "/D5'") (class "Default")
      (node (ref "IC15") (pin "14") (pinfunction "DO_14") (pintype "bidirectional"))
      (node (ref "IC15") (pin "2") (pinfunction "DI_2") (pintype "bidirectional"))
      (node (ref "IC3") (pin "30") (pinfunction "D5_30") (pintype "bidirectional"))
      (node (ref "R6") (pin "1") (pinfunction "1_1") (pintype "passive"))
    )
    (net (code "49") (name "/D6") (class "Default")
      (node (ref "IC1") (pin "10") (pinfunction "D6_10") (pintype "bidirectional"))
      (node (ref "IC10") (pin "5") (pinfunction "Y3_5") (pintype "tri_state"))
      (node (ref "IC2") (pin "18") (pinfunction "O6_18") (pintype "tri_state"))
      (node (ref "IC22") (pin "15") (pinfunction "I/O3_15") (pintype "bidirectional"))
      (node (ref "IC24") (pin "15") (pinfunction "I/O3_15") (pintype "bidirectional"))
      (node (ref "R23") (pin "1") (pinfunction "1_1") (pintype "passive"))
      (node (ref "R7") (pin "2") (pinfunction "2_2") (pintype "passive"))
      (node (ref "U$1") (pin "9B") (pinfunction "EDGE_9B") (pintype "bidirectional"))
    )
    (net (code "50") (name "/D6'") (class "Default")
      (node (ref "IC14") (pin "14") (pinfunction "DO_14") (pintype "bidirectional"))
      (node (ref "IC14") (pin "2") (pinfunction "DI_2") (pintype "bidirectional"))
      (node (ref "IC3") (pin "31") (pinfunction "D6_31") (pintype "bidirectional"))
      (node (ref "R7") (pin "1") (pinfunction "1_1") (pintype "passive"))
    )
    (net (code "51") (name "/D7") (class "Default")
      (node (ref "IC1") (pin "13") (pinfunction "D7_13") (pintype "bidirectional"))
      (node (ref "IC10") (pin "3") (pinfunction "Y4_3") (pintype "tri_state"))
      (node (ref "IC2") (pin "19") (pinfunction "O7_19") (pintype "tri_state"))
      (node (ref "IC22") (pin "17") (pinfunction "I/O4_17") (pintype "bidirectional"))
      (node (ref "IC24") (pin "17") (pinfunction "I/O4_17") (pintype "bidirectional"))
      (node (ref "R24") (pin "1") (pinfunction "1_1") (pintype "passive"))
      (node (ref "R8") (pin "2") (pinfunction "2_2") (pintype "passive"))
      (node (ref "U$1") (pin "3B") (pinfunction "EDGE_3B") (pintype "bidirectional"))
    )
    (net (code "52") (name "/D7'") (class "Default")
      (node (ref "IC13") (pin "14") (pinfunction "DO_14") (pintype "bidirectional"))
      (node (ref "IC13") (pin "2") (pinfunction "DI_2") (pintype "bidirectional"))
      (node (ref "IC3") (pin "32") (pinfunction "D7_32") (pintype "bidirectional"))
      (node (ref "R8") (pin "1") (pinfunction "1_1") (pintype "passive"))
    )
    (net (code "53") (name "/MREQ'") (class "Default")
      (node (ref "D10") (pin "C") (pinfunction "K_C") (pintype "bidirectional"))
      (node (ref "IC3") (pin "15") (pinfunction "~{MREQ}_15") (pintype "input"))
      (node (ref "R34") (pin "2") (pinfunction "2_2") (pintype "passive"))
    )
    (net (code "54") (name "/N$33") (class "Default")
      (node (ref "C26") (pin "1") (pinfunction "1_1") (pintype "passive"))
      (node (ref "C27") (pin "1") (pinfunction "1_1") (pintype "passive"))
      (node (ref "IC13") (pin "1") (pinfunction "VBB_1") (pintype "input"))
      (node (ref "IC14") (pin "1") (pinfunction "VBB_1") (pintype "input"))
      (node (ref "IC15") (pin "1") (pinfunction "VBB_1") (pintype "input"))
      (node (ref "IC16") (pin "1") (pinfunction "VBB_1") (pintype "input"))
      (node (ref "IC17") (pin "1") (pinfunction "VBB_1") (pintype "input"))
      (node (ref "IC18") (pin "1") (pinfunction "VBB_1") (pintype "input"))
      (node (ref "IC19") (pin "1") (pinfunction "VBB_1") (pintype "input"))
      (node (ref "IC20") (pin "1") (pinfunction "VBB_1") (pintype "input"))
      (node (ref "J3") (pin "2") (pinfunction "2_2") (pintype "passive"))
    )
    (net (code "55") (name "/RESET") (class "Default")
      (node (ref "D10") (pin "A") (pinfunction "A_A") (pintype "bidirectional"))
      (node (ref "IC28") (pin "12") (pinfunction "O_12") (pintype "output"))
    )
    (net (code "56") (name "/SNDIN") (class "Default")
      (node (ref "C54") (pin "1") (pinfunction "1_1") (pintype "passive"))
      (node (ref "C57") (pin "1") (pinfunction "1_1") (pintype "passive"))
      (node (ref "D13") (pin "A") (pinfunction "A_A") (pintype "bidirectional"))
      (node (ref "D14") (pin "C") (pinfunction "C_C") (pintype "passive"))
      (node (ref "Q7") (pin "2") (pinfunction "B_2") (pintype "passive"))
      (node (ref "R40") (pin "1") (pinfunction "1_1") (pintype "passive"))
      (node (ref "R41") (pin "2") (pinfunction "2_2") (pintype "passive"))
      (node (ref "R42") (pin "2") (pinfunction "2_2") (pintype "passive"))
      (node (ref "TP3") (pin "TP") (pinfunction "TP_TP") (pintype "input"))
    )
    (net (code "57") (name "/{slash}INT") (class "Default")
      (node (ref "IC1") (pin "16") (pinfunction "~{INT}_16") (pintype "input"))
      (node (ref "R25") (pin "2") (pinfunction "2_2") (pintype "passive"))
      (node (ref "TP10") (pin "TP") (pinfunction "TP_TP") (pintype "input"))
      (node (ref "U$1") (pin "13B") (pinfunction "EDGE_13B") (pintype "bidirectional"))
    )
    (net (code "58") (name "/~{A}{slash}B") (class "Default")
      (node (ref "IC27") (pin "3") (pinfunction "O_3") (pintype "output"))
      (node (ref "IC6") (pin "1") (pinfunction "~{A}/B_1") (pintype "input"))
      (node (ref "IC7") (pin "1") (pinfunction "~{A}/B_1") (pintype "input"))
      (node (ref "R45") (pin "1") (pinfunction "1_1") (pintype "passive"))
    )
    (net (code "59") (name "/~{CAS0}") (class "Default")
      (node (ref "IC23") (pin "1") (pinfunction "~{OE}_1") (pintype "input"))
      (node (ref "IC23") (pin "16") (pinfunction "~{CAS}_16") (pintype "input"))
      (node (ref "IC24") (pin "1") (pinfunction "~{OE}_1") (pintype "input"))
      (node (ref "IC24") (pin "16") (pinfunction "~{CAS}_16") (pintype "input"))
      (node (ref "IC25") (pin "8") (pinfunction "O_8") (pintype "output"))
    )
    (net (code "60") (name "/~{CAS1}") (class "Default")
      (node (ref "IC21") (pin "1") (pinfunction "~{OE}_1") (pintype "input"))
      (node (ref "IC21") (pin "16") (pinfunction "~{CAS}_16") (pintype "input"))
      (node (ref "IC22") (pin "1") (pinfunction "~{OE}_1") (pintype "input"))
      (node (ref "IC22") (pin "16") (pinfunction "~{CAS}_16") (pintype "input"))
      (node (ref "IC25") (pin "6") (pinfunction "O_6") (pintype "output"))
    )
    (net (code "61") (name "/~{IORQGE}") (class "Default")
      (node (ref "IC3") (pin "2") (pinfunction "~{CS}_2") (pintype "input"))
      (node (ref "Q1") (pin "1") (pinfunction "E_1") (pintype "passive"))
      (node (ref "R27") (pin "2") (pinfunction "2_2") (pintype "passive"))
      (node (ref "U$1") (pin "13A") (pinfunction "EDGE_13A") (pintype "bidirectional"))
    )
    (net (code "62") (name "/~{IORQ}") (class "Default")
      (node (ref "IC1") (pin "20") (pinfunction "~{IORQ}_20") (pintype "output"))
      (node (ref "R27") (pin "1") (pinfunction "1_1") (pintype "passive"))
      (node (ref "U$1") (pin "17B") (pinfunction "EDGE_17B") (pintype "bidirectional"))
    )
    (net (code "63") (name "/~{KBD}") (class "Default")
      (node (ref "IC10") (pin "1") (pinfunction "G_1") (pintype "input"))
      (node (ref "IC10") (pin "19") (pinfunction "G_19") (pintype "input"))
      (node (ref "IC3") (pin "10") (pinfunction "~{KBD}_10") (pintype "output"))
    )
    (net (code "64") (name "/~{MREQ}") (class "Default")
      (node (ref "IC1") (pin "19") (pinfunction "~{MREQ}_19") (pintype "output"))
      (node (ref "IC2") (pin "22") (pinfunction "~{OE}_22") (pintype "input"))
      (node (ref "IC27") (pin "4") (pinfunction "I0_4") (pintype "input"))
      (node (ref "R34") (pin "1") (pinfunction "1_1") (pintype "passive"))
      (node (ref "U$1") (pin "16B") (pinfunction "EDGE_16B") (pintype "bidirectional"))
    )
    (net (code "65") (name "/~{RAS}") (class "Default")
      (node (ref "IC21") (pin "5") (pinfunction "~{RAS}_5") (pintype "input"))
      (node (ref "IC22") (pin "5") (pinfunction "~{RAS}_5") (pintype "input"))
      (node (ref "IC23") (pin "5") (pinfunction "~{RAS}_5") (pintype "input"))
      (node (ref "IC24") (pin "5") (pinfunction "~{RAS}_5") (pintype "input"))
      (node (ref "IC27") (pin "6") (pinfunction "O_6") (pintype "output"))
      (node (ref "IC27") (pin "9") (pinfunction "I0_9") (pintype "input"))
      (node (ref "R28") (pin "1") (pinfunction "1_1") (pintype "passive"))
    )
    (net (code "66") (name "/~{RD}") (class "Default")
      (node (ref "IC1") (pin "21") (pinfunction "~{RD}_21") (pintype "output"))
      (node (ref "IC25") (pin "2") (pinfunction "I1_2") (pintype "input"))
      (node (ref "IC3") (pin "17") (pinfunction "~{RD}_17") (pintype "input"))
      (node (ref "J9") (pin "1") (pinfunction "1_1") (pintype "passive"))
      (node (ref "U$1") (pin "18B") (pinfunction "EDGE_18B") (pintype "bidirectional"))
    )
    (net (code "67") (name "/~{RESET}") (class "Default")
      (node (ref "C17") (pin "1") (pinfunction "1_1") (pintype "passive"))
      (node (ref "IC1") (pin "26") (pinfunction "~{RESET}_26") (pintype "input"))
      (node (ref "IC28") (pin "13") (pinfunction "I_13") (pintype "input"))
      (node (ref "R29") (pin "1") (pinfunction "1_1") (pintype "passive"))
      (node (ref "U$1") (pin "20A") (pinfunction "EDGE_20A") (pintype "bidirectional"))
      (node (ref "X8") (pin "1") (pinfunction "1_1") (pintype "passive"))
    )
    (net (code "68") (name "/~{RFSH}") (class "Default")
      (node (ref "IC1") (pin "28") (pinfunction "~{RFSH}_28") (pintype "output"))
      (node (ref "IC26") (pin "13") (pinfunction "I1_13") (pintype "input"))
      (node (ref "IC26") (pin "2") (pinfunction "I1_2") (pintype "input"))
      (node (ref "IC5") (pin "11") (pinfunction "CLK_11") (pintype "input"))
      (node (ref "U$1") (pin "25B") (pinfunction "EDGE_25B") (pintype "bidirectional"))
    )
    (net (code "69") (name "/~{ROMCS}") (class "Default")
      (node (ref "IC2") (pin "20") (pinfunction "~{CE}_20") (pintype "input"))
      (node (ref "R26") (pin "2") (pinfunction "2_2") (pintype "passive"))
      (node (ref "TP9") (pin "TP") (pinfunction "TP_TP") (pintype "input"))
      (node (ref "U$1") (pin "25A") (pinfunction "EDGE_25A") (pintype "bidirectional"))
    )
    (net (code "70") (name "/~{ULAINT}") (class "Default")
      (node (ref "IC3") (pin "34") (pinfunction "~{INT}_34") (pintype "output"))
      (node (ref "R25") (pin "1") (pinfunction "1_1") (pintype "passive"))
    )
    (net (code "71") (name "/~{VCAS}") (class "Default")
      (node (ref "IC13") (pin "15") (pinfunction "~{CAS}_15") (pintype "input"))
      (node (ref "IC14") (pin "15") (pinfunction "~{CAS}_15") (pintype "input"))
      (node (ref "IC15") (pin "15") (pinfunction "~{CAS}_15") (pintype "input"))
      (node (ref "IC16") (pin "15") (pinfunction "~{CAS}_15") (pintype "input"))
      (node (ref "IC17") (pin "15") (pinfunction "~{CAS}_15") (pintype "input"))
      (node (ref "IC18") (pin "15") (pinfunction "~{CAS}_15") (pintype "input"))
      (node (ref "IC19") (pin "15") (pinfunction "~{CAS}_15") (pintype "input"))
      (node (ref "IC20") (pin "15") (pinfunction "~{CAS}_15") (pintype "input"))
      (node (ref "IC3") (pin "12") (pinfunction "~{VCAS}_12") (pintype "output"))
      (node (ref "TP5") (pin "TP") (pinfunction "TP_TP") (pintype "input"))
    )
    (net (code "72") (name "/~{VRAS}") (class "Default")
      (node (ref "IC13") (pin "4") (pinfunction "~{RAS}_4") (pintype "input"))
      (node (ref "IC14") (pin "4") (pinfunction "~{RAS}_4") (pintype "input"))
      (node (ref "IC15") (pin "4") (pinfunction "~{RAS}_4") (pintype "input"))
      (node (ref "IC16") (pin "4") (pinfunction "~{RAS}_4") (pintype "input"))
      (node (ref "IC17") (pin "4") (pinfunction "~{RAS}_4") (pintype "input"))
      (node (ref "IC18") (pin "4") (pinfunction "~{RAS}_4") (pintype "input"))
      (node (ref "IC19") (pin "4") (pinfunction "~{RAS}_4") (pintype "input"))
      (node (ref "IC20") (pin "4") (pinfunction "~{RAS}_4") (pintype "input"))
      (node (ref "IC3") (pin "13") (pinfunction "~{VRAS}_13") (pintype "output"))
      (node (ref "R16") (pin "2") (pinfunction "2_2") (pintype "passive"))
      (node (ref "TP4") (pin "TP") (pinfunction "TP_TP") (pintype "input"))
    )
    (net (code "73") (name "/~{VWR}") (class "Default")
      (node (ref "IC13") (pin "3") (pinfunction "~{WE}_3") (pintype "input"))
      (node (ref "IC14") (pin "3") (pinfunction "~{WE}_3") (pintype "input"))
      (node (ref "IC15") (pin "3") (pinfunction "~{WE}_3") (pintype "input"))
      (node (ref "IC16") (pin "3") (pinfunction "~{WE}_3") (pintype "input"))
      (node (ref "IC17") (pin "3") (pinfunction "~{WE}_3") (pintype "input"))
      (node (ref "IC18") (pin "3") (pinfunction "~{WE}_3") (pintype "input"))
      (node (ref "IC19") (pin "3") (pinfunction "~{WE}_3") (pintype "input"))
      (node (ref "IC20") (pin "3") (pinfunction "~{WE}_3") (pintype "input"))
      (node (ref "IC3") (pin "14") (pinfunction "~{VWR}_14") (pintype "output"))
      (node (ref "TP6") (pin "TP") (pinfunction "TP_TP") (pintype "input"))
    )
    (net (code "74") (name "/~{WR}") (class "Default")
      (node (ref "IC1") (pin "22") (pinfunction "~{WR}_22") (pintype "output"))
      (node (ref "IC21") (pin "4") (pinfunction "~{WE}_4") (pintype "input"))
      (node (ref "IC22") (pin "4") (pinfunction "~{WE}_4") (pintype "input"))
      (node (ref "IC23") (pin "4") (pinfunction "~{WE}_4") (pintype "input"))
      (node (ref "IC24") (pin "4") (pinfunction "~{WE}_4") (pintype "input"))
      (node (ref "IC25") (pin "1") (pinfunction "I0_1") (pintype "input"))
      (node (ref "IC3") (pin "16") (pinfunction "~{WR}_16") (pintype "input"))
      (node (ref "U$1") (pin "19B") (pinfunction "EDGE_19B") (pintype "bidirectional"))
    )
    (net (code "75") (name "AUDIO") (class "Default")
      (node (ref "J4") (pin "1") (pinfunction "1_1") (pintype "passive"))
      (node (ref "J8") (pin "3") (pinfunction "3_3") (pintype "passive"))
      (node (ref "R52") (pin "1") (pinfunction "1_1") (pintype "passive"))
      (node (ref "R53") (pin "1") (pinfunction "1_1") (pintype "passive"))
    )
    (net (code "76") (name "GND") (class "Default")
      (node (ref "C1") (pin "-") (pinfunction "-_-") (pintype "passive"))
      (node (ref "C10") (pin "2") (pinfunction "2_2") (pintype "passive"))
      (node (ref "C11") (pin "2") (pinfunction "2_2") (pintype "passive"))
      (node (ref "C12") (pin "1") (pinfunction "1_1") (pintype "passive"))
      (node (ref "C13") (pin "1") (pinfunction "1_1") (pintype "passive"))
      (node (ref "C14") (pin "1") (pinfunction "1_1") (pintype "passive"))
      (node (ref "C15") (pin "2") (pinfunction "2_2") (pintype "passive"))
      (node (ref "C16") (pin "2") (pinfunction "2_2") (pintype "passive"))
      (node (ref "C17") (pin "2") (pinfunction "2_2") (pintype "passive"))
      (node (ref "C18") (pin "2") (pinfunction "2_2") (pintype "passive"))
      (node (ref "C19") (pin "2") (pinfunction "2_2") (pintype "passive"))
      (node (ref "C2") (pin "-") (pinfunction "-_-") (pintype "passive"))
      (node (ref "C20") (pin "2") (pinfunction "2_2") (pintype "passive"))
      (node (ref "C21") (pin "2") (pinfunction "2_2") (pintype "passive"))
      (node (ref "C22") (pin "1") (pinfunction "1_1") (pintype "passive"))
      (node (ref "C23") (pin "2") (pinfunction "2_2") (pintype "passive"))
      (node (ref "C24") (pin "1") (pinfunction "1_1") (pintype "passive"))
      (node (ref "C25") (pin "2") (pinfunction "2_2") (pintype "passive"))
      (node (ref "C26") (pin "2") (pinfunction "2_2") (pintype "passive"))
      (node (ref "C27") (pin "2") (pinfunction "2_2") (pintype "passive"))
      (node (ref "C28") (pin "2") (pinfunction "2_2") (pintype "passive"))
      (node (ref "C29") (pin "1") (pinfunction "1_1") (pintype "passive"))
      (node (ref "C3") (pin "1") (pinfunction "1_1") (pintype "passive"))
      (node (ref "C30") (pin "2") (pinfunction "2_2") (pintype "passive"))
      (node (ref "C31") (pin "1") (pinfunction "1_1") (pintype "passive"))
      (node (ref "C32") (pin "1") (pinfunction "1_1") (pintype "passive"))
      (node (ref "C33") (pin "1") (pinfunction "1_1") (pintype "passive"))
      (node (ref "C40") (pin "1") (pinfunction "1_1") (pintype "passive"))
      (node (ref "C43") (pin "1") (pinfunction "1_1") (pintype "passive"))
      (node (ref "C44") (pin "2") (pinfunction "2_2") (pintype "passive"))
      (node (ref "C45") (pin "2") (pinfunction "2_2") (pintype "passive"))
      (node (ref "C46") (pin "2") (pinfunction "2_2") (pintype "passive"))
      (node (ref "C49") (pin "+") (pinfunction "+_+") (pintype "passive"))
      (node (ref "C50") (pin "2") (pinfunction "2_2") (pintype "passive"))
      (node (ref "C52") (pin "-") (pinfunction "-_-") (pintype "passive"))
      (node (ref "C53") (pin "-") (pinfunction "-_-") (pintype "passive"))
      (node (ref "C56") (pin "1") (pinfunction "1_1") (pintype "passive"))
      (node (ref "C57") (pin "2") (pinfunction "2_2") (pintype "passive"))
      (node (ref "C6") (pin "1") (pinfunction "1_1") (pintype "passive"))
      (node (ref "C8") (pin "1") (pinfunction "1_1") (pintype "passive"))
      (node (ref "D14") (pin "A") (pinfunction "A_A") (pintype "passive"))
      (node (ref "D16") (pin "A") (pinfunction "A_A") (pintype "bidirectional"))
      (node (ref "D18") (pin "A") (pinfunction "A_A") (pintype "bidirectional"))
      (node (ref "D20") (pin "C") (pinfunction "K_C") (pintype "bidirectional"))
      (node (ref "D21") (pin "C") (pinfunction "K_C") (pintype "bidirectional"))
      (node (ref "D24") (pin "A") (pinfunction "A_A") (pintype "bidirectional"))
      (node (ref "IC1") (pin "29") (pinfunction "GND_29") (pintype "power_in"))
      (node (ref "IC10") (pin "10") (pinfunction "GND_10") (pintype "power_in"))
      (node (ref "IC11") (pin "10") (pinfunction "GND_10") (pintype "power_in"))
      (node (ref "IC12") (pin "5") (pinfunction "GND_5") (pintype "power_in"))
      (node (ref "IC13") (pin "16") (pinfunction "VSS_16") (pintype "power_in"))
      (node (ref "IC14") (pin "16") (pinfunction "VSS_16") (pintype "power_in"))
      (node (ref "IC15") (pin "16") (pinfunction "VSS_16") (pintype "power_in"))
      (node (ref "IC16") (pin "16") (pinfunction "VSS_16") (pintype "power_in"))
      (node (ref "IC17") (pin "16") (pinfunction "VSS_16") (pintype "power_in"))
      (node (ref "IC18") (pin "16") (pinfunction "VSS_16") (pintype "power_in"))
      (node (ref "IC19") (pin "16") (pinfunction "VSS_16") (pintype "power_in"))
      (node (ref "IC2") (pin "14") (pinfunction "GND_14") (pintype "power_in"))
      (node (ref "IC20") (pin "16") (pinfunction "VSS_16") (pintype "power_in"))
      (node (ref "IC21") (pin "18") (pinfunction "GND_18") (pintype "power_in"))
      (node (ref "IC22") (pin "18") (pinfunction "GND_18") (pintype "power_in"))
      (node (ref "IC23") (pin "18") (pinfunction "GND_18") (pintype "power_in"))
      (node (ref "IC24") (pin "18") (pinfunction "GND_18") (pintype "power_in"))
      (node (ref "IC25") (pin "7") (pinfunction "GND_7") (pintype "power_in"))
      (node (ref "IC26") (pin "7") (pinfunction "GND_7") (pintype "power_in"))
      (node (ref "IC27") (pin "5") (pinfunction "I1_5") (pintype "input"))
      (node (ref "IC27") (pin "7") (pinfunction "GND_7") (pintype "power_in"))
      (node (ref "IC28") (pin "7") (pinfunction "GND_7") (pintype "power_in"))
      (node (ref "IC29") (pin "GND") (pinfunction "GND_GND") (pintype "input"))
      (node (ref "IC3") (pin "20") (pinfunction "GND_20") (pintype "power_in"))
      (node (ref "IC4") (pin "7") (pinfunction "GND_7") (pintype "power_in"))
      (node (ref "IC5") (pin "7") (pinfunction "GND_7") (pintype "power_in"))
      (node (ref "IC6") (pin "15") (pinfunction "G_15") (pintype "input"))
      (node (ref "IC6") (pin "8") (pinfunction "GND_8") (pintype "power_in"))
      (node (ref "IC7") (pin "15") (pinfunction "G_15") (pintype "input"))
      (node (ref "IC7") (pin "8") (pinfunction "GND_8") (pintype "power_in"))
      (node (ref "IC8") (pin "15") (pinfunction "G_15") (pintype "input"))
      (node (ref "IC8") (pin "8") (pinfunction "GND_8") (pintype "power_in"))
      (node (ref "IC9") (pin "15") (pinfunction "G_15") (pintype "input"))
      (node (ref "IC9") (pin "8") (pinfunction "GND_8") (pintype "power_in"))
      (node (ref "J10") (pin "1") (pinfunction "1_1") (pintype "passive"))
      (node (ref "Q2") (pin "1") (pinfunction "E_1") (pintype "passive"))
      (node (ref "Q4") (pin "1") (pinfunction "E_1") (pintype "passive"))
      (node (ref "Q6") (pin "C") (pinfunction "C_C") (pintype "passive"))
      (node (ref "Q7") (pin "1") (pinfunction "E_1") (pintype "passive"))
      (node (ref "R33") (pin "2") (pinfunction "2_2") (pintype "passive"))
      (node (ref "R41") (pin "1") (pinfunction "1_1") (pintype "passive"))
      (node (ref "R47") (pin "1") (pinfunction "1_1") (pintype "passive"))
      (node (ref "R50") (pin "1") (pinfunction "1_1") (pintype "passive"))
      (node (ref "R53") (pin "2") (pinfunction "2_2") (pintype "passive"))
      (node (ref "R55") (pin "2") (pinfunction "2_2") (pintype "passive"))
      (node (ref "R65") (pin "2") (pinfunction "2_2") (pintype "passive"))
      (node (ref "R69") (pin "1") (pinfunction "1_1") (pintype "passive"))
      (node (ref "R70") (pin "1") (pinfunction "1_1") (pintype "passive"))
      (node (ref "R73_") (pin "2") (pinfunction "2_2") (pintype "passive"))
      (node (ref "R76") (pin "2") (pinfunction "2_2") (pintype "passive"))
      (node (ref "U$1") (pin "14A") (pinfunction "EDGE_14A") (pintype "bidirectional"))
      (node (ref "U$1") (pin "6A") (pinfunction "EDGE_6A") (pintype "bidirectional"))
      (node (ref "U$1") (pin "7A") (pinfunction "EDGE_7A") (pintype "bidirectional"))
      (node (ref "X1") (pin "SLEEVE") (pinfunction "SLEEVE_SLEEVE") (pintype "passive"))
      (node (ref "X2") (pin "SLEEVE") (pinfunction "SLEEVE_SLEEVE") (pintype "passive"))
      (node (ref "X3") (pin "SLEEVE") (pinfunction "SLEEVE_SLEEVE") (pintype "passive"))
      (node (ref "X4") (pin "2") (pinfunction "2_2") (pintype "passive"))
      (node (ref "X4") (pin "2@1") (pinfunction "2_2@1") (pintype "passive"))
      (node (ref "X4") (pin "2@2") (pinfunction "2_2@2") (pintype "passive"))
      (node (ref "X5") (pin "2") (pinfunction "2_2") (pintype "passive"))
      (node (ref "X5") (pin "2@1") (pinfunction "2_2@1") (pintype "passive"))
      (node (ref "X5") (pin "2@2") (pinfunction "2_2@2") (pintype "passive"))
      (node (ref "X6") (pin "2") (pinfunction "2_2") (pintype "passive"))
      (node (ref "X8") (pin "2") (pinfunction "2_2") (pintype "passive"))
    )
    (net (code "77") (name "Net-(C5-Pad+)") (class "Default")
      (node (ref "C5") (pin "+") (pinfunction "+_+") (pintype "passive"))
      (node (ref "R42") (pin "1") (pinfunction "1_1") (pintype "passive"))
    )
    (net (code "78") (name "Net-(C5-Pad-)") (class "Default")
      (node (ref "C5") (pin "-") (pinfunction "-_-") (pintype "passive"))
      (node (ref "J5") (pin "1") (pinfunction "1_1") (pintype "passive"))
      (node (ref "R70") (pin "2") (pinfunction "2_2") (pintype "passive"))
      (node (ref "X2") (pin "TIP") (pinfunction "TIP_TIP") (pintype "passive"))
    )
    (net (code "79") (name "Net-(C7-Pad1)") (class "Default")
      (node (ref "C7") (pin "1") (pinfunction "1_1") (pintype "passive"))
      (node (ref "XTAL") (pin "2") (pinfunction "2_2") (pintype "passive"))
    )
    (net (code "80") (name "Net-(C8-Pad2)") (class "Default")
      (node (ref "C8") (pin "2") (pinfunction "2_2") (pintype "passive"))
      (node (ref "Q3") (pin "B") (pinfunction "B_B") (pintype "passive"))
      (node (ref "R44") (pin "2") (pinfunction "2_2") (pintype "passive"))
      (node (ref "XTAL") (pin "1") (pinfunction "1_1") (pintype "passive"))
    )
    (net (code "81") (name "Net-(C36-Pad2)") (class "Default")
      (node (ref "C36") (pin "2") (pinfunction "2_2") (pintype "passive"))
      (node (ref "C54") (pin "2") (pinfunction "2_2") (pintype "passive"))
      (node (ref "C55") (pin "1") (pinfunction "1_1") (pintype "passive"))
      (node (ref "R52") (pin "2") (pinfunction "2_2") (pintype "passive"))
    )
    (net (code "82") (name "Net-(C37-Pad1)") (class "Default")
      (node (ref "C37") (pin "1") (pinfunction "1_1") (pintype "passive"))
      (node (ref "C38") (pin "2") (pinfunction "2_2") (pintype "passive"))
      (node (ref "R55") (pin "1") (pinfunction "1_1") (pintype "passive"))
    )
    (net (code "83") (name "Net-(C38-Pad1)") (class "Default")
      (node (ref "C38") (pin "1") (pinfunction "1_1") (pintype "passive"))
      (node (ref "C39") (pin "2") (pinfunction "2_2") (pintype "passive"))
      (node (ref "R56") (pin "1") (pinfunction "1_1") (pintype "passive"))
    )
    (net (code "84") (name "Net-(C39-Pad1)") (class "Default")
      (node (ref "C39") (pin "1") (pinfunction "1_1") (pintype "passive"))
      (node (ref "L2") (pin "2") (pinfunction "2_2") (pintype "passive"))
    )
    (net (code "85") (name "Net-(C49-Pad-)") (class "Default")
      (node (ref "C49") (pin "-") (pinfunction "-_-") (pintype "passive"))
      (node (ref "D19") (pin "A") (pinfunction "A_A") (pintype "bidirectional"))
      (node (ref "R67") (pin "2") (pinfunction "2_2") (pintype "passive"))
    )
    (net (code "86") (name "Net-(C56-Pad2)") (class "Default")
      (node (ref "C56") (pin "2") (pinfunction "2_2") (pintype "passive"))
      (node (ref "L2") (pin "1") (pinfunction "1_1") (pintype "passive"))
      (node (ref "R71") (pin "1") (pinfunction "1_1") (pintype "passive"))
      (node (ref "R72") (pin "2") (pinfunction "2_2") (pintype "passive"))
    )
    (net (code "87") (name "Net-(C58-Pad+)") (class "Default")
      (node (ref "C58") (pin "+") (pinfunction "+_+") (pintype "passive"))
      (node (ref "R77") (pin "2") (pinfunction "2_2") (pintype "passive"))
    )
    (net (code "88") (name "Net-(C58-Pad-)") (class "Default")
      (node (ref "C58") (pin "-") (pinfunction "-_-") (pintype "passive"))
      (node (ref "J8") (pin "1") (pinfunction "1_1") (pintype "passive"))
      (node (ref "X4") (pin "1") (pinfunction "1_1") (pintype "passive"))
    )
    (net (code "89") (name "Net-(D2-PadA)") (class "Default")
      (node (ref "D2") (pin "A") (pinfunction "A_A") (pintype "bidirectional"))
      (node (ref "KB2") (pin "3") (pinfunction "3_3") (pintype "passive"))
    )
    (net (code "90") (name "Net-(D3-PadA)") (class "Default")
      (node (ref "D3") (pin "A") (pinfunction "A_A") (pintype "bidirectional"))
      (node (ref "KB2") (pin "6") (pinfunction "6_6") (pintype "passive"))
    )
    (net (code "91") (name "Net-(D4-PadA)") (class "Default")
      (node (ref "D4") (pin "A") (pinfunction "A_A") (pintype "bidirectional"))
      (node (ref "KB2") (pin "7") (pinfunction "7_7") (pintype "passive"))
    )
    (net (code "92") (name "Net-(D7-PadA)") (class "Default")
      (node (ref "D7") (pin "A") (pinfunction "A_A") (pintype "bidirectional"))
      (node (ref "KB2") (pin "4") (pinfunction "4_4") (pintype "passive"))
    )
    (net (code "93") (name "Net-(D8-PadA)") (class "Default")
      (node (ref "D8") (pin "A") (pinfunction "A_A") (pintype "bidirectional"))
      (node (ref "KB2") (pin "2") (pinfunction "2_2") (pintype "passive"))
    )
    (net (code "94") (name "Net-(D9-PadA)") (class "Default")
      (node (ref "D9") (pin "A") (pinfunction "A_A") (pintype "bidirectional"))
      (node (ref "KB2") (pin "1") (pinfunction "1_1") (pintype "passive"))
    )
    (net (code "95") (name "Net-(D11-K)") (class "Default")
      (node (ref "D11") (pin "C") (pinfunction "K_C") (pintype "bidirectional"))
      (node (ref "D12") (pin "C") (pinfunction "K_C") (pintype "bidirectional"))
      (node (ref "IC27") (pin "11") (pinfunction "O_11") (pintype "output"))
      (node (ref "R26") (pin "1") (pinfunction "1_1") (pintype "passive"))
      (node (ref "R33") (pin "1") (pinfunction "1_1") (pintype "passive"))
    )
    (net (code "96") (name "Net-(D16-K)") (class "Default")
      (node (ref "C36") (pin "1") (pinfunction "1_1") (pintype "passive"))
      (node (ref "D15") (pin "A") (pinfunction "A_A") (pintype "bidirectional"))
      (node (ref "D16") (pin "C") (pinfunction "K_C") (pintype "bidirectional"))
      (node (ref "IC3") (pin "24") (pinfunction "BEEP_24") (pintype "output"))
      (node (ref "TP7") (pin "TP") (pinfunction "TP_TP") (pintype "input"))
    )
    (net (code "97") (name "Net-(D19-K)") (class "Default")
      (node (ref "C48") (pin "2") (pinfunction "2_2") (pintype "passive"))
      (node (ref "D19") (pin "C") (pinfunction "K_C") (pintype "bidirectional"))
      (node (ref "D20") (pin "A") (pinfunction "A_A") (pintype "bidirectional"))
    )
    (net (code "98") (name "Net-(D22-K)") (class "Default")
      (node (ref "C51") (pin "2") (pinfunction "2_2") (pintype "passive"))
      (node (ref "D22") (pin "C") (pinfunction "K_C") (pintype "bidirectional"))
      (node (ref "D23") (pin "A") (pinfunction "A_A") (pintype "bidirectional"))
    )
    (net (code "99") (name "Net-(D23-K)") (class "Default")
      (node (ref "C52") (pin "+") (pinfunction "+_+") (pintype "passive"))
      (node (ref "D23") (pin "C") (pinfunction "K_C") (pintype "bidirectional"))
      (node (ref "R68") (pin "2") (pinfunction "2_2") (pintype "passive"))
    )
    (net (code "100") (name "Net-(D27-K)") (class "Default")
      (node (ref "D25") (pin "C") (pinfunction "C_C") (pintype "passive"))
      (node (ref "D26") (pin "C") (pinfunction "C_C") (pintype "passive"))
      (node (ref "D27") (pin "C") (pinfunction "K_C") (pintype "bidirectional"))
      (node (ref "IC3") (pin "18") (pinfunction "BRIGHT_18") (pintype "output"))
    )
    (net (code "101") (name "Net-(IC1-CLK)") (class "Default")
      (node (ref "IC1") (pin "6") (pinfunction "CLK_6") (pintype "input"))
      (node (ref "Q2") (pin "3") (pinfunction "C_3") (pintype "passive"))
      (node (ref "R48") (pin "1") (pinfunction "1_1") (pintype "passive"))
      (node (ref "TP1") (pin "TP") (pinfunction "TP_TP") (pintype "input"))
    )
    (net (code "102") (name "Net-(IC1-~{BUSAK})") (class "Default")
      (node (ref "IC1") (pin "23") (pinfunction "~{BUSAK}_23") (pintype "output"))
      (node (ref "U$1") (pin "26A") (pinfunction "EDGE_26A") (pintype "bidirectional"))
    )
    (net (code "103") (name "Net-(IC1-~{BUSRQ})") (class "Default")
      (node (ref "IC1") (pin "25") (pinfunction "~{BUSRQ}_25") (pintype "input"))
      (node (ref "R30") (pin "2") (pinfunction "2_2") (pintype "passive"))
      (node (ref "U$1") (pin "19A") (pinfunction "EDGE_19A") (pintype "bidirectional"))
    )
    (net (code "104") (name "Net-(IC1-~{HALT})") (class "Default")
      (node (ref "IC1") (pin "18") (pinfunction "~{HALT}_18") (pintype "output"))
      (node (ref "U$1") (pin "15B") (pinfunction "EDGE_15B") (pintype "bidirectional"))
    )
    (net (code "105") (name "Net-(IC1-~{M1})") (class "Default")
      (node (ref "IC1") (pin "27") (pinfunction "~{M1}_27") (pintype "output"))
      (node (ref "U$1") (pin "24B") (pinfunction "EDGE_24B") (pintype "bidirectional"))
    )
    (net (code "106") (name "Net-(IC1-~{NMI})") (class "Default")
      (node (ref "IC1") (pin "17") (pinfunction "~{NMI}_17") (pintype "input"))
      (node (ref "R31") (pin "2") (pinfunction "2_2") (pintype "passive"))
      (node (ref "U$1") (pin "14B") (pinfunction "EDGE_14B") (pintype "bidirectional"))
    )
    (net (code "107") (name "Net-(IC1-~{WAIT})") (class "Default")
      (node (ref "IC1") (pin "24") (pinfunction "~{WAIT}_24") (pintype "input"))
      (node (ref "R32") (pin "2") (pinfunction "2_2") (pintype "passive"))
      (node (ref "U$1") (pin "21B") (pinfunction "EDGE_21B") (pintype "bidirectional"))
    )
    (net (code "108") (name "Net-(IC2-~{PGM})") (class "Default")
      (node (ref "IC2") (pin "27") (pinfunction "~{PGM}_27") (pintype "input"))
      (node (ref "J9") (pin "2") (pinfunction "2_2") (pintype "passive"))
    )
    (net (code "109") (name "Net-(IC3-MIC)") (class "Default")
      (node (ref "IC3") (pin "23") (pinfunction "MIC_23") (pintype "output"))
      (node (ref "R46") (pin "2") (pinfunction "2_2") (pintype "passive"))
    )
    (net (code "110") (name "Net-(IC3-~{50}{slash}60HZ)") (class "Default")
      (node (ref "IC3") (pin "1") (pinfunction "~{50}/60HZ_1") (pintype "input"))
      (node (ref "J10") (pin "2") (pinfunction "2_2") (pintype "passive"))
    )
    (net (code "111") (name "Net-(IC4B-D)") (class "Default")
      (node (ref "IC4") (pin "12") (pinfunction "D_12") (pintype "input"))
      (node (ref "IC4") (pin "8") (pinfunction "~{Q}_8") (pintype "output"))
    )
    (net (code "112") (name "Net-(IC4B-Q)") (class "Default")
      (node (ref "IC4") (pin "9") (pinfunction "Q_9") (pintype "output"))
      (node (ref "J7") (pin "1") (pinfunction "1_1") (pintype "passive"))
    )
    (net (code "113") (name "Net-(IC5A-CLK)") (class "Default")
      (node (ref "IC5") (pin "3") (pinfunction "CLK_3") (pintype "input"))
      (node (ref "IC5") (pin "9") (pinfunction "Q_9") (pintype "output"))
    )
    (net (code "114") (name "Net-(IC5A-D)") (class "Default")
      (node (ref "IC5") (pin "2") (pinfunction "D_2") (pintype "input"))
      (node (ref "IC5") (pin "6") (pinfunction "~{Q}_6") (pintype "output"))
    )
    (net (code "115") (name "Net-(IC8A-1Y)") (class "Default")
      (node (ref "IC8") (pin "4") (pinfunction "1Y_4") (pintype "output"))
      (node (ref "R15") (pin "2") (pinfunction "2_2") (pintype "passive"))
    )
    (net (code "116") (name "Net-(IC8A-2Y)") (class "Default")
      (node (ref "IC8") (pin "7") (pinfunction "2Y_7") (pintype "output"))
      (node (ref "R14") (pin "2") (pinfunction "2_2") (pintype "passive"))
    )
    (net (code "117") (name "Net-(IC8A-3Y)") (class "Default")
      (node (ref "IC8") (pin "9") (pinfunction "3Y_9") (pintype "output"))
      (node (ref "R12") (pin "2") (pinfunction "2_2") (pintype "passive"))
    )
    (net (code "118") (name "Net-(IC8A-4Y)") (class "Default")
      (node (ref "IC8") (pin "12") (pinfunction "4Y_12") (pintype "output"))
      (node (ref "R13") (pin "2") (pinfunction "2_2") (pintype "passive"))
    )
    (net (code "119") (name "Net-(IC8A-~{A}{slash}B)") (class "Default")
      (node (ref "IC8") (pin "1") (pinfunction "~{A}/B_1") (pintype "input"))
      (node (ref "IC9") (pin "1") (pinfunction "~{A}/B_1") (pintype "input"))
      (node (ref "R16") (pin "1") (pinfunction "1_1") (pintype "passive"))
    )
    (net (code "120") (name "Net-(IC9A-2Y)") (class "Default")
      (node (ref "IC9") (pin "7") (pinfunction "2Y_7") (pintype "output"))
      (node (ref "R11") (pin "2") (pinfunction "2_2") (pintype "passive"))
    )
    (net (code "121") (name "Net-(IC9A-3Y)") (class "Default")
      (node (ref "IC9") (pin "9") (pinfunction "3Y_9") (pintype "output"))
      (node (ref "R9") (pin "2") (pinfunction "2_2") (pintype "passive"))
    )
    (net (code "122") (name "Net-(IC9A-4Y)") (class "Default")
      (node (ref "IC9") (pin "12") (pinfunction "4Y_12") (pintype "output"))
      (node (ref "R10") (pin "2") (pinfunction "2_2") (pintype "passive"))
    )
    (net (code "123") (name "Net-(IC10A-A1)") (class "Default")
      (node (ref "IC10") (pin "2") (pinfunction "A1_2") (pintype "input"))
      (node (ref "KB1") (pin "5") (pinfunction "5_5") (pintype "passive"))
      (node (ref "R39") (pin "2") (pinfunction "2_2") (pintype "passive"))
      (node (ref "X7") (pin "6") (pinfunction "M_6") (pintype "passive"))
    )
    (net (code "124") (name "Net-(IC10A-A2)") (class "Default")
      (node (ref "IC10") (pin "4") (pinfunction "A2_4") (pintype "input"))
      (node (ref "KB1") (pin "4") (pinfunction "4_4") (pintype "passive"))
      (node (ref "R38") (pin "2") (pinfunction "2_2") (pintype "passive"))
      (node (ref "X7") (pin "1") (pinfunction "M_1") (pintype "passive"))
    )
    (net (code "125") (name "Net-(IC10A-A3)") (class "Default")
      (node (ref "IC10") (pin "6") (pinfunction "A3_6") (pintype "input"))
      (node (ref "KB1") (pin "3") (pinfunction "3_3") (pintype "passive"))
      (node (ref "R35") (pin "2") (pinfunction "2_2") (pintype "passive"))
      (node (ref "X7") (pin "2") (pinfunction "M_2") (pintype "passive"))
    )
    (net (code "126") (name "Net-(IC10A-A4)") (class "Default")
      (node (ref "IC10") (pin "8") (pinfunction "A4_8") (pintype "input"))
      (node (ref "KB1") (pin "2") (pinfunction "2_2") (pintype "passive"))
      (node (ref "R36") (pin "2") (pinfunction "2_2") (pintype "passive"))
      (node (ref "X7") (pin "4") (pinfunction "M_4") (pintype "passive"))
    )
    (net (code "127") (name "Net-(IC10B-A1)") (class "Default")
      (node (ref "IC10") (pin "11") (pinfunction "A1_11") (pintype "input"))
      (node (ref "KB1") (pin "1") (pinfunction "1_1") (pintype "passive"))
      (node (ref "R37") (pin "2") (pinfunction "2_2") (pintype "passive"))
      (node (ref "X7") (pin "3") (pinfunction "M_3") (pintype "passive"))
    )
    (net (code "128") (name "Net-(IC10B-A3)") (class "Default")
      (node (ref "IC10") (pin "15") (pinfunction "A3_15") (pintype "input"))
      (node (ref "Q7") (pin "3") (pinfunction "C_3") (pintype "passive"))
      (node (ref "R74_") (pin "1") (pinfunction "1_1") (pintype "passive"))
    )
    (net (code "129") (name "Net-(IC11-B-Y)") (class "Default")
      (node (ref "C45") (pin "1") (pinfunction "1_1") (pintype "passive"))
      (node (ref "IC11") (pin "4") (pinfunction "B-Y_4") (pintype "output"))
      (node (ref "IC12") (pin "4") (pinfunction "B-Y_4") (pintype "input"))
    )
    (net (code "130") (name "Net-(IC11-B1)") (class "Default")
      (node (ref "IC11") (pin "17") (pinfunction "B3_17") (pintype "input"))
      (node (ref "IC11") (pin "19") (pinfunction "B1_19") (pintype "input"))
      (node (ref "IC3") (pin "22") (pinfunction "BLUE_22") (pintype "output"))
      (node (ref "R75") (pin "2") (pinfunction "2_2") (pintype "passive"))
    )
    (net (code "131") (name "Net-(IC11-B2)") (class "Default")
      (node (ref "D27") (pin "A") (pinfunction "A_A") (pintype "bidirectional"))
      (node (ref "IC11") (pin "18") (pinfunction "B2_18") (pintype "input"))
      (node (ref "R75") (pin "1") (pinfunction "1_1") (pintype "passive"))
    )
    (net (code "132") (name "Net-(IC11-BLANK)") (class "Default")
      (node (ref "IC11") (pin "8") (pinfunction "SYNC_8") (pintype "input"))
      (node (ref "IC11") (pin "9") (pinfunction "BLANK_9") (pintype "input"))
      (node (ref "IC3") (pin "33") (pinfunction "SYNC_33") (pintype "output"))
      (node (ref "TP8") (pin "TP") (pinfunction "TP_TP") (pintype "input"))
    )
    (net (code "133") (name "Net-(IC11-CREF)") (class "Default")
      (node (ref "C46") (pin "1") (pinfunction "1_1") (pintype "passive"))
      (node (ref "IC11") (pin "7") (pinfunction "CREF_7") (pintype "input"))
      (node (ref "IC12") (pin "12") (pinfunction "Y_12") (pintype "input"))
    )
    (net (code "134") (name "Net-(IC11-G1)") (class "Default")
      (node (ref "IC11") (pin "14") (pinfunction "G3_14") (pintype "input"))
      (node (ref "IC11") (pin "16") (pinfunction "G1_16") (pintype "input"))
      (node (ref "IC3") (pin "19") (pinfunction "GREEN_19") (pintype "output"))
      (node (ref "R73") (pin "2") (pinfunction "2_2") (pintype "passive"))
    )
    (net (code "135") (name "Net-(IC11-G2)") (class "Default")
      (node (ref "D25") (pin "A") (pinfunction "A_A") (pintype "passive"))
      (node (ref "IC11") (pin "15") (pinfunction "G2_15") (pintype "input"))
      (node (ref "R73") (pin "1") (pinfunction "1_1") (pintype "passive"))
    )
    (net (code "136") (name "Net-(IC11-GATE)") (class "Default")
      (node (ref "IC11") (pin "1") (pinfunction "GATE_1") (pintype "input"))
      (node (ref "IC28") (pin "6") (pinfunction "O_6") (pintype "output"))
    )
    (net (code "137") (name "Net-(IC11-H{slash}2)") (class "Default")
      (node (ref "IC11") (pin "2") (pinfunction "H/2_2") (pintype "input"))
      (node (ref "J7") (pin "2") (pinfunction "2_2") (pintype "passive"))
    )
    (net (code "138") (name "Net-(IC11-R-Y)") (class "Default")
      (node (ref "C44") (pin "1") (pinfunction "1_1") (pintype "passive"))
      (node (ref "IC11") (pin "3") (pinfunction "R-Y_3") (pintype "output"))
      (node (ref "IC12") (pin "2") (pinfunction "R-Y_2") (pintype "input"))
    )
    (net (code "139") (name "Net-(IC11-R1)") (class "Default")
      (node (ref "IC11") (pin "11") (pinfunction "R3_11") (pintype "input"))
      (node (ref "IC11") (pin "13") (pinfunction "R1_13") (pintype "input"))
      (node (ref "IC3") (pin "21") (pinfunction "RED_21") (pintype "output"))
      (node (ref "R74") (pin "2") (pinfunction "2_2") (pintype "passive"))
    )
    (net (code "140") (name "Net-(IC11-R2)") (class "Default")
      (node (ref "D26") (pin "A") (pinfunction "A_A") (pintype "passive"))
      (node (ref "IC11") (pin "12") (pinfunction "R2_12") (pintype "input"))
      (node (ref "R74") (pin "1") (pinfunction "1_1") (pintype "passive"))
    )
    (net (code "141") (name "Net-(IC11-Y)") (class "Default")
      (node (ref "IC11") (pin "6") (pinfunction "Y_6") (pintype "output"))
      (node (ref "R63") (pin "2") (pinfunction "2_2") (pintype "passive"))
    )
    (net (code "142") (name "Net-(IC12-CR_LAG)") (class "Default")
      (node (ref "C40") (pin "2") (pinfunction "2_2") (pintype "passive"))
      (node (ref "IC12") (pin "18") (pinfunction "CR_LAG_18") (pintype "output"))
      (node (ref "R56") (pin "2") (pinfunction "2_2") (pintype "passive"))
    )
    (net (code "143") (name "Net-(IC12-CR_LEAD)") (class "Default")
      (node (ref "C37") (pin "2") (pinfunction "2_2") (pintype "passive"))
      (node (ref "IC12") (pin "1") (pinfunction "CR_LEAD_1") (pintype "input"))
    )
    (net (code "144") (name "Net-(IC12-CR_OSC)") (class "Default")
      (node (ref "IC12") (pin "17") (pinfunction "CR_OSC_17") (pintype "input"))
      (node (ref "R72") (pin "1") (pinfunction "1_1") (pintype "passive"))
      (node (ref "R73_") (pin "1") (pinfunction "1_1") (pintype "passive"))
    )
    (net (code "145") (name "Net-(IC12-CR_SUBC)") (class "Default")
      (node (ref "IC12") (pin "13") (pinfunction "CR_SUBC_13") (pintype "input"))
      (node (ref "Q8") (pin "2") (pinfunction "B_2") (pintype "passive"))
      (node (ref "R63") (pin "1") (pinfunction "1_1") (pintype "passive"))
    )
    (net (code "146") (name "Net-(IC12-TNKA1)") (class "Default")
      (node (ref "IC12") (pin "8") (pinfunction "TNKA1_8") (pintype "output"))
      (node (ref "IC12") (pin "9") (pinfunction "TNKA2_9") (pintype "input"))
    )
    (net (code "147") (name "Net-(IC12-TNKB1)") (class "Default")
      (node (ref "IC12") (pin "6") (pinfunction "TNKB1_6") (pintype "output"))
      (node (ref "IC12") (pin "7") (pinfunction "TNKB2_7") (pintype "input"))
    )
    (net (code "148") (name "Net-(IC25A-O)") (class "Default")
      (node (ref "IC25") (pin "12") (pinfunction "I0_12") (pintype "input"))
      (node (ref "IC25") (pin "3") (pinfunction "O_3") (pintype "output"))
    )
    (net (code "149") (name "Net-(IC25B-I1)") (class "Default")
      (node (ref "IC25") (pin "10") (pinfunction "I1_10") (pintype "input"))
      (node (ref "IC25") (pin "5") (pinfunction "I1_5") (pintype "input"))
      (node (ref "IC28") (pin "4") (pinfunction "O_4") (pintype "output"))
    )
    (net (code "150") (name "Net-(IC25C-I0)") (class "Default")
      (node (ref "IC25") (pin "9") (pinfunction "I0_9") (pintype "input"))
      (node (ref "IC28") (pin "2") (pinfunction "O_2") (pintype "output"))
    )
    (net (code "151") (name "Net-(IC25D-O)") (class "Default")
      (node (ref "IC25") (pin "11") (pinfunction "O_11") (pintype "output"))
      (node (ref "IC27") (pin "1") (pinfunction "I0_1") (pintype "input"))
    )
    (net (code "152") (name "Net-(IC26A-O)") (class "Default")
      (node (ref "IC26") (pin "3") (pinfunction "O_3") (pintype "output"))
      (node (ref "IC26") (pin "4") (pinfunction "I0_4") (pintype "input"))
    )
    (net (code "153") (name "Net-(IC26B-I1)") (class "Default")
      (node (ref "IC26") (pin "5") (pinfunction "I1_5") (pintype "input"))
      (node (ref "IC5") (pin "5") (pinfunction "Q_5") (pintype "output"))
    )
    (net (code "154") (name "Net-(IC26B-O)") (class "Default")
      (node (ref "IC26") (pin "6") (pinfunction "O_6") (pintype "output"))
      (node (ref "IC26") (pin "9") (pinfunction "I0_9") (pintype "input"))
    )
    (net (code "155") (name "Net-(IC26C-I1)") (class "Default")
      (node (ref "IC26") (pin "10") (pinfunction "I1_10") (pintype "input"))
      (node (ref "IC26") (pin "11") (pinfunction "O_11") (pintype "output"))
    )
    (net (code "156") (name "Net-(IC27A-I1)") (class "Default")
      (node (ref "C10") (pin "1") (pinfunction "1_1") (pintype "passive"))
      (node (ref "IC27") (pin "2") (pinfunction "I1_2") (pintype "input"))
      (node (ref "R28") (pin "2") (pinfunction "2_2") (pintype "passive"))
    )
    (net (code "157") (name "Net-(IC27C-I1)") (class "Default")
      (node (ref "C11") (pin "1") (pinfunction "1_1") (pintype "passive"))
      (node (ref "IC27") (pin "10") (pinfunction "I1_10") (pintype "input"))
      (node (ref "J6") (pin "2") (pinfunction "2_2") (pintype "passive"))
      (node (ref "R45") (pin "2") (pinfunction "2_2") (pintype "passive"))
    )
    (net (code "158") (name "Net-(IC27C-O)") (class "Default")
      (node (ref "IC27") (pin "8") (pinfunction "O_8") (pintype "output"))
      (node (ref "IC28") (pin "3") (pinfunction "I_3") (pintype "input"))
    )
    (net (code "159") (name "Net-(IC28C-I)") (class "Default")
      (node (ref "IC28") (pin "5") (pinfunction "I_5") (pintype "input"))
      (node (ref "IC3") (pin "35") (pinfunction "GATE_35") (pintype "output"))
      (node (ref "IC4") (pin "11") (pinfunction "CLK_11") (pintype "input"))
    )
    (net (code "160") (name "Net-(IC28D-I)") (class "Default")
      (node (ref "C6") (pin "2") (pinfunction "2_2") (pintype "passive"))
      (node (ref "C7") (pin "2") (pinfunction "2_2") (pintype "passive"))
      (node (ref "IC28") (pin "9") (pinfunction "I_9") (pintype "input"))
      (node (ref "Q3") (pin "C") (pinfunction "C_C") (pintype "passive"))
      (node (ref "R43") (pin "1") (pinfunction "1_1") (pintype "passive"))
      (node (ref "R44") (pin "1") (pinfunction "1_1") (pintype "passive"))
    )
    (net (code "161") (name "Net-(IC28D-O)") (class "Default")
      (node (ref "IC28") (pin "11") (pinfunction "I_11") (pintype "input"))
      (node (ref "IC28") (pin "8") (pinfunction "O_8") (pintype "output"))
      (node (ref "JP") (pin "3") (pinfunction "3_3") (pintype "passive"))
    )
    (net (code "162") (name "Net-(IC28E-O)") (class "Default")
      (node (ref "IC28") (pin "10") (pinfunction "O_10") (pintype "output"))
      (node (ref "IC3") (pin "11") (pinfunction "CLK_11") (pintype "input"))
      (node (ref "JP") (pin "1") (pinfunction "1_1") (pintype "passive"))
      (node (ref "JP") (pin "2") (pinfunction "2_2") (pintype "passive"))
      (node (ref "TP2") (pin "TP") (pinfunction "TP_TP") (pintype "input"))
    )
    (net (code "163") (name "Net-(J1-Pad1)") (class "Default")
      (node (ref "J1") (pin "1") (pinfunction "1_1") (pintype "passive"))
      (node (ref "X1") (pin "RING") (pinfunction "RING_RING") (pintype "passive"))
    )
    (net (code "164") (name "Net-(J4-Pad2)") (class "Default")
      (node (ref "J4") (pin "2") (pinfunction "2_2") (pintype "passive"))
      (node (ref "X3") (pin "TIP") (pinfunction "TIP_TIP") (pintype "passive"))
    )
    (net (code "165") (name "Net-(J5-Pad2)") (class "Default")
      (node (ref "J5") (pin "2") (pinfunction "2_2") (pintype "passive"))
      (node (ref "X2") (pin "RING") (pinfunction "RING_RING") (pintype "passive"))
    )
    (net (code "166") (name "Net-(J7-Pad3)") (class "Default")
      (node (ref "J7") (pin "3") (pinfunction "3_3") (pintype "passive"))
      (node (ref "R54") (pin "2") (pinfunction "2_2") (pintype "passive"))
    )
    (net (code "167") (name "Net-(J8-Pad2)") (class "Default")
      (node (ref "J8") (pin "2") (pinfunction "2_2") (pintype "passive"))
      (node (ref "X5") (pin "1") (pinfunction "1_1") (pintype "passive"))
    )
    (net (code "168") (name "Net-(Q2-B)") (class "Default")
      (node (ref "C9") (pin "1") (pinfunction "1_1") (pintype "passive"))
      (node (ref "Q2") (pin "2") (pinfunction "B_2") (pintype "passive"))
      (node (ref "R49") (pin "1") (pinfunction "1_1") (pintype "passive"))
      (node (ref "R50") (pin "2") (pinfunction "2_2") (pintype "passive"))
    )
    (net (code "169") (name "Net-(Q3-PadE)") (class "Default")
      (node (ref "Q3") (pin "E") (pinfunction "E_E") (pintype "passive"))
      (node (ref "R47") (pin "2") (pinfunction "2_2") (pintype "passive"))
    )
    (net (code "170") (name "Net-(Q4-B)") (class "Default")
      (node (ref "C47") (pin "2") (pinfunction "2_2") (pintype "passive"))
      (node (ref "Q4") (pin "2") (pinfunction "B_2") (pintype "passive"))
      (node (ref "R64") (pin "1") (pinfunction "1_1") (pintype "passive"))
      (node (ref "R65") (pin "1") (pinfunction "1_1") (pintype "passive"))
    )
    (net (code "171") (name "Net-(Q4-C)") (class "Default")
      (node (ref "Q4") (pin "3") (pinfunction "C_3") (pintype "passive"))
      (node (ref "Q5") (pin "B") (pinfunction "B_B") (pintype "passive"))
      (node (ref "Q6") (pin "B") (pinfunction "B_B") (pintype "passive"))
      (node (ref "R66") (pin "2") (pinfunction "2_2") (pintype "passive"))
    )
    (net (code "172") (name "Net-(Q8-E)") (class "Default")
      (node (ref "Q8") (pin "1") (pinfunction "E_1") (pintype "passive"))
      (node (ref "R76") (pin "1") (pinfunction "1_1") (pintype "passive"))
      (node (ref "R77") (pin "1") (pinfunction "1_1") (pintype "passive"))
    )
    (net (code "173") (name "Net-(R46-Pad1)") (class "Default")
      (node (ref "R46") (pin "1") (pinfunction "1_1") (pintype "passive"))
      (node (ref "R69") (pin "2") (pinfunction "2_2") (pintype "passive"))
      (node (ref "X3") (pin "RING") (pinfunction "RING_RING") (pintype "passive"))
    )
    (net (code "174") (name "Net-(U$1H-EDGE)") (class "Default")
      (node (ref "J6") (pin "1") (pinfunction "1_1") (pintype "passive"))
      (node (ref "U$1") (pin "17A") (pinfunction "EDGE_17A") (pintype "bidirectional"))
    )
    (net (code "175") (name "Net-(U$1Y-EDGE)") (class "Default")
      (node (ref "C55") (pin "2") (pinfunction "2_2") (pintype "passive"))
      (node (ref "U$1") (pin "4B") (pinfunction "EDGE_4B") (pintype "bidirectional"))
    )
    (net (code "176") (name "Net-(X7E-M)") (class "Default")
      (node (ref "D6") (pin "A") (pinfunction "A_A") (pintype "bidirectional"))
      (node (ref "KB2") (pin "5") (pinfunction "5_5") (pintype "passive"))
      (node (ref "X7") (pin "5") (pinfunction "M_5") (pintype "passive"))
      (node (ref "X7") (pin "8") (pinfunction "M_8") (pintype "passive"))
      (node (ref "X7") (pin "9") (pinfunction "M_9") (pintype "passive"))
    )
    (net (code "177") (name "Net-(X7G-M)") (class "Default")
      (node (ref "D5") (pin "A") (pinfunction "A_A") (pintype "bidirectional"))
      (node (ref "KB2") (pin "8") (pinfunction "8_8") (pintype "passive"))
      (node (ref "X7") (pin "7") (pinfunction "M_7") (pintype "passive"))
    )
    (net (code "178") (name "V+") (class "Default")
      (node (ref "C2") (pin "+") (pinfunction "+_+") (pintype "passive"))
      (node (ref "C3") (pin "2") (pinfunction "2_2") (pintype "passive"))
      (node (ref "D22") (pin "A") (pinfunction "A_A") (pintype "bidirectional"))
      (node (ref "IC29") (pin "IN") (pinfunction "IN_IN") (pintype "input"))
      (node (ref "J1") (pin "2") (pinfunction "2_2") (pintype "passive"))
      (node (ref "J2") (pin "1") (pinfunction "1_1") (pintype "passive"))
      (node (ref "Q5") (pin "C") (pinfunction "C_C") (pintype "passive"))
      (node (ref "R66") (pin "1") (pinfunction "1_1") (pintype "passive"))
      (node (ref "U$1") (pin "4A") (pinfunction "EDGE_4A") (pintype "bidirectional"))
      (node (ref "X1") (pin "TIP") (pinfunction "TIP_TIP") (pintype "passive"))
    )
    (net (code "179") (name "VDD") (class "Default")
      (node (ref "C23") (pin "1") (pinfunction "1_1") (pintype "passive"))
      (node (ref "C25") (pin "1") (pinfunction "1_1") (pintype "passive"))
      (node (ref "C28") (pin "1") (pinfunction "1_1") (pintype "passive"))
      (node (ref "C30") (pin "1") (pinfunction "1_1") (pintype "passive"))
      (node (ref "IC13") (pin "8") (pinfunction "VDD_8") (pintype "power_in"))
      (node (ref "IC14") (pin "8") (pinfunction "VDD_8") (pintype "power_in"))
      (node (ref "IC15") (pin "8") (pinfunction "VDD_8") (pintype "power_in"))
      (node (ref "IC16") (pin "8") (pinfunction "VDD_8") (pintype "power_in"))
      (node (ref "IC17") (pin "8") (pinfunction "VDD_8") (pintype "power_in"))
      (node (ref "IC18") (pin "8") (pinfunction "VDD_8") (pintype "power_in"))
      (node (ref "IC19") (pin "8") (pinfunction "VDD_8") (pintype "power_in"))
      (node (ref "IC20") (pin "8") (pinfunction "VDD_8") (pintype "power_in"))
      (node (ref "J2") (pin "2") (pinfunction "2_2") (pintype "passive"))
    )
    (net (code "180") (name "unconnected-(IC4A-Q-Pad5)") (class "Default")
      (node (ref "IC4") (pin "5") (pinfunction "Q_5") (pintype "output"))
    )
    (net (code "181") (name "unconnected-(IC4A-~{Q}-Pad6)") (class "Default")
      (node (ref "IC4") (pin "6") (pinfunction "~{Q}_6") (pintype "output"))
    )
    (net (code "182") (name "unconnected-(IC5B-~{Q}-Pad8)") (class "Default")
      (node (ref "IC5") (pin "8") (pinfunction "~{Q}_8") (pintype "output"))
    )
    (net (code "183") (name "unconnected-(IC6A-1A-Pad2)") (class "Default")
      (node (ref "IC6") (pin "2") (pinfunction "1A_2") (pintype "input"))
    )
    (net (code "184") (name "unconnected-(IC6A-1B-Pad3)") (class "Default")
      (node (ref "IC6") (pin "3") (pinfunction "1B_3") (pintype "input"))
    )
    (net (code "185") (name "unconnected-(IC6A-1Y-Pad4)") (class "Default")
      (node (ref "IC6") (pin "4") (pinfunction "1Y_4") (pintype "output"))
    )
    (net (code "186") (name "unconnected-(IC6A-3A-Pad11)") (class "Default")
      (node (ref "IC6") (pin "11") (pinfunction "3A_11") (pintype "input"))
    )
    (net (code "187") (name "unconnected-(IC6A-3B-Pad10)") (class "Default")
      (node (ref "IC6") (pin "10") (pinfunction "3B_10") (pintype "input"))
    )
    (net (code "188") (name "unconnected-(IC6A-3Y-Pad9)") (class "Default")
      (node (ref "IC6") (pin "9") (pinfunction "3Y_9") (pintype "output"))
    )
    (net (code "189") (name "unconnected-(IC9A-1A-Pad2)") (class "Default")
      (node (ref "IC9") (pin "2") (pinfunction "1A_2") (pintype "input"))
    )
    (net (code "190") (name "unconnected-(IC9A-1B-Pad3)") (class "Default")
      (node (ref "IC9") (pin "3") (pinfunction "1B_3") (pintype "input"))
    )
    (net (code "191") (name "unconnected-(IC9A-1Y-Pad4)") (class "Default")
      (node (ref "IC9") (pin "4") (pinfunction "1Y_4") (pintype "output"))
    )
    (net (code "192") (name "unconnected-(IC12-CHA_O-Pad11)") (class "Default")
      (node (ref "IC12") (pin "11") (pinfunction "CHA_O_11") (pintype "input"))
    )
    (net (code "193") (name "unconnected-(IC12-CHB_O-Pad10)") (class "Default")
      (node (ref "IC12") (pin "10") (pinfunction "CHB_O_10") (pintype "input"))
    )
    (net (code "194") (name "unconnected-(IC12-SNDTK-Pad15)") (class "Default")
      (node (ref "IC12") (pin "15") (pinfunction "SNDTK_15") (pintype "input"))
    )
    (net (code "195") (name "unconnected-(U$1AX-EDGE-Pad28B)") (class "Default")
      (node (ref "U$1") (pin "28B") (pinfunction "EDGE_28B") (pintype "bidirectional"))
    )
    (net (code "196") (name "unconnected-(U$1F-EDGE-Pad15A)") (class "Default")
      (node (ref "U$1") (pin "15A") (pinfunction "EDGE_15A") (pintype "bidirectional"))
    )
    (net (code "197") (name "unconnected-(U$1G-EDGE-Pad16A)") (class "Default")
      (node (ref "U$1") (pin "16A") (pinfunction "EDGE_16A") (pintype "bidirectional"))
    )
    (net (code "198") (name "unconnected-(U$1I-EDGE-Pad18A)") (class "Default")
      (node (ref "U$1") (pin "18A") (pinfunction "EDGE_18A") (pintype "bidirectional"))
    )
  )
)
